# MainMaster.net
KiCad netlist of a schematic drawn in Altium Designer
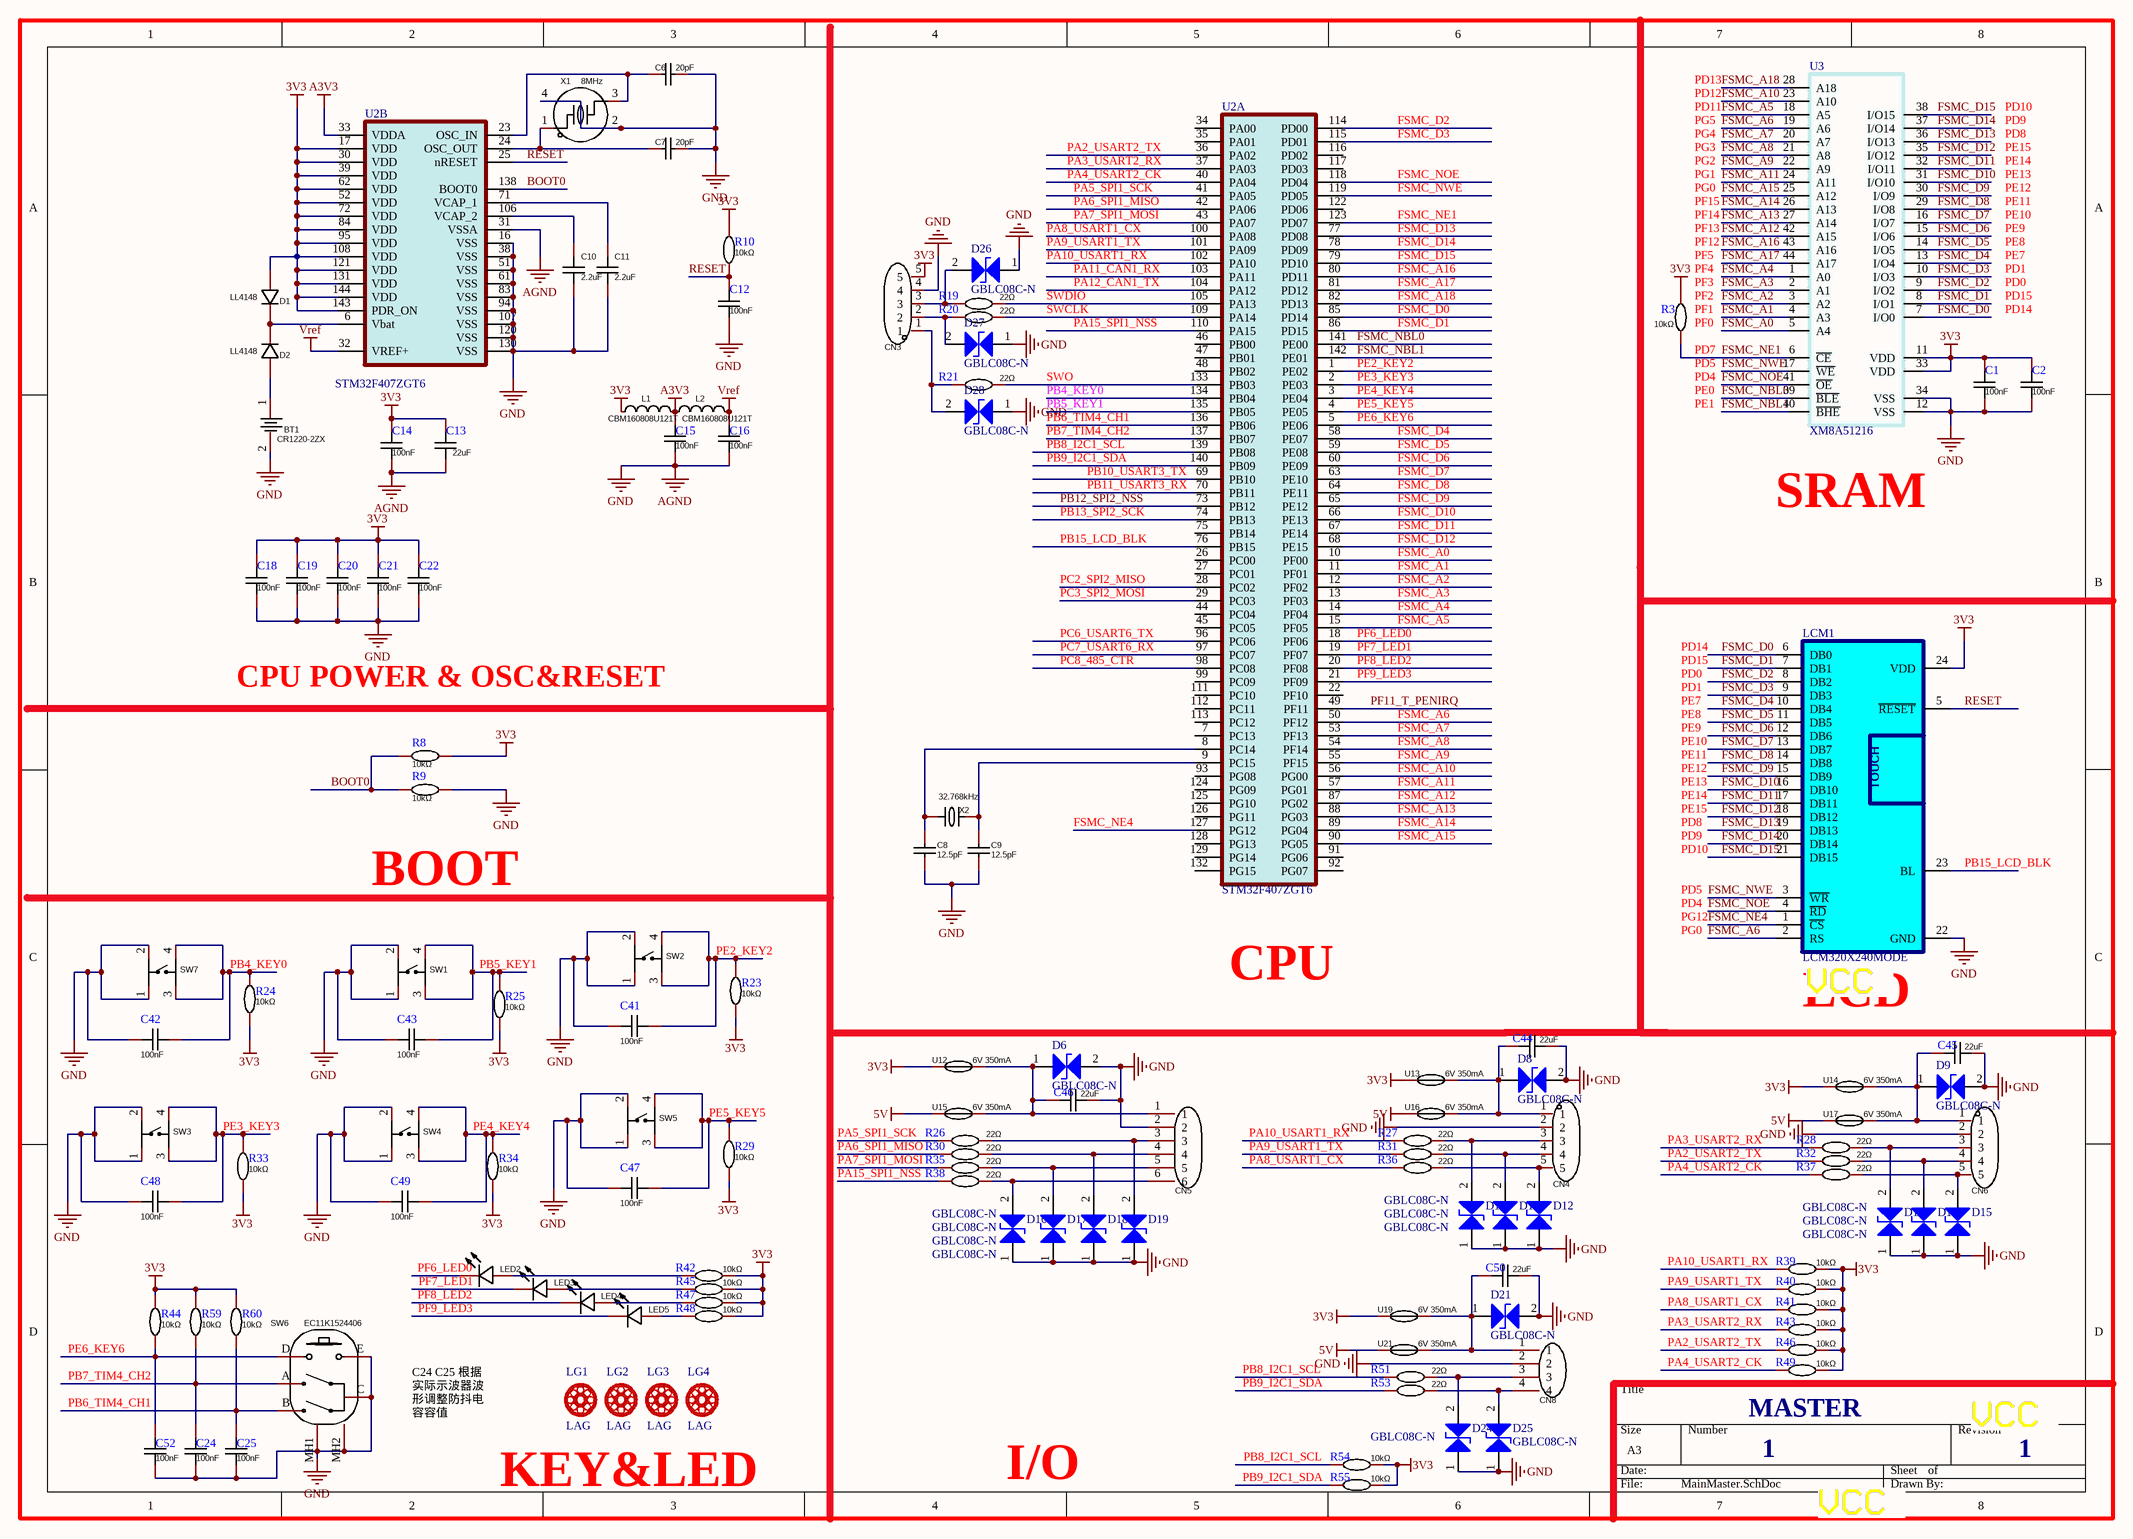
[diagram p0: MainMaster.SchDoc]

(export (version "E")
  (design (tool "Eeschema 10.0.6"))
  (components
    (comp (ref "BT1")
      (value "CR1220-2ZX")
      (footprint "LI1220_1")
      (fields (field (name "NAME") "CR1220-2ZX") (field (name "MANUFACTURER") "Q&J"))
      (libsource (lib "altium-import") (part "root_3_CR1220-2ZX_"))
    )
    (comp (ref "C1")
      (value "CC0603KRX7R9BB104")
      (footprint "C0603")
      (fields
        (field (name "NAME") "100nF")
        (field (name "MANUFACTURER") "YAGEO(国巨)")
        (field (name "TOLERANCE") "±10%")
      )
      (libsource (lib "altium-import") (part "root_1_CC0603KRX7R9BB104_"))
    )
    (comp (ref "C2")
      (value "CC0603KRX7R9BB104")
      (footprint "C0603")
      (fields
        (field (name "NAME") "100nF")
        (field (name "MANUFACTURER") "YAGEO(国巨)")
        (field (name "TOLERANCE") "±10%")
      )
      (libsource (lib "altium-import") (part "root_1_CC0603KRX7R9BB104_"))
    )
    (comp (ref "C6")
      (value "CC0603JRNPO9BN200")
      (footprint "C0603")
      (fields
        (field (name "NAME") "20pF")
        (field (name "MANUFACTURER") "YAGEO(国巨)")
        (field (name "TOLERANCE") "±5%")
      )
      (libsource (lib "altium-import") (part "root_0_CC0603JRNPO9BN200_"))
    )
    (comp (ref "C7")
      (value "CC0603JRNPO9BN200")
      (footprint "C0603")
      (fields
        (field (name "NAME") "20pF")
        (field (name "MANUFACTURER") "YAGEO(国巨)")
        (field (name "TOLERANCE") "±5%")
      )
      (libsource (lib "altium-import") (part "root_0_CC0603JRNPO9BN200_"))
    )
    (comp (ref "C8")
      (value "CC0603JRNPO9BN200")
      (footprint "C0603")
      (fields
        (field (name "NAME") "12.5pF")
        (field (name "MANUFACTURER") "YAGEO(国巨)")
        (field (name "TOLERANCE") "±5%")
      )
      (libsource (lib "altium-import") (part "root_1_CC0603JRNPO9BN200_"))
    )
    (comp (ref "C9")
      (value "CC0603JRNPO9BN200")
      (footprint "C0603")
      (fields
        (field (name "NAME") "12.5pF")
        (field (name "MANUFACTURER") "YAGEO(国巨)")
        (field (name "TOLERANCE") "±5%")
      )
      (libsource (lib "altium-import") (part "root_1_CC0603JRNPO9BN200_"))
    )
    (comp (ref "C10")
      (value "CL10A225KA8NNNC")
      (footprint "C0603")
      (fields
        (field (name "NAME") "2.2uF")
        (field (name "MANUFACTURER") "SAMSUNG(三星)")
        (field (name "TOLERANCE") "±10%")
      )
      (libsource (lib "altium-import") (part "root_1_CL10A225KA8NNNC_"))
    )
    (comp (ref "C11")
      (value "CL10A225KA8NNNC")
      (footprint "C0603")
      (fields
        (field (name "NAME") "2.2uF")
        (field (name "MANUFACTURER") "SAMSUNG(三星)")
        (field (name "TOLERANCE") "±10%")
      )
      (libsource (lib "altium-import") (part "root_1_CL10A225KA8NNNC_"))
    )
    (comp (ref "C12")
      (value "CC0603KRX7R9BB104")
      (footprint "C0603")
      (fields
        (field (name "NAME") "100nF")
        (field (name "MANUFACTURER") "YAGEO(国巨)")
        (field (name "TOLERANCE") "±10%")
      )
      (libsource (lib "altium-import") (part "root_1_CC0603KRX7R9BB104_"))
    )
    (comp (ref "C13")
      (value "CC0603KRX7R9BB104")
      (footprint "C1210")
      (fields
        (field (name "NAME") "22uF")
        (field (name "MANUFACTURER") "YAGEO(国巨)")
        (field (name "TOLERANCE") "±10%")
      )
      (libsource (lib "altium-import") (part "root_1_CC0603KRX7R9BB104_"))
    )
    (comp (ref "C14")
      (value "CC0603KRX7R9BB104")
      (footprint "C0603")
      (fields
        (field (name "NAME") "100nF")
        (field (name "MANUFACTURER") "YAGEO(国巨)")
        (field (name "TOLERANCE") "±10%")
      )
      (libsource (lib "altium-import") (part "root_1_CC0603KRX7R9BB104_"))
    )
    (comp (ref "C15")
      (value "CC0603KRX7R9BB104")
      (footprint "C0603")
      (fields
        (field (name "NAME") "100nF")
        (field (name "MANUFACTURER") "YAGEO(国巨)")
        (field (name "TOLERANCE") "±10%")
      )
      (libsource (lib "altium-import") (part "root_1_CC0603KRX7R9BB104_"))
    )
    (comp (ref "C16")
      (value "CC0603KRX7R9BB104")
      (footprint "C0603")
      (fields
        (field (name "NAME") "100nF")
        (field (name "MANUFACTURER") "YAGEO(国巨)")
        (field (name "TOLERANCE") "±10%")
      )
      (libsource (lib "altium-import") (part "root_1_CC0603KRX7R9BB104_"))
    )
    (comp (ref "C18")
      (value "CC0603KRX7R9BB104")
      (footprint "C0603")
      (fields
        (field (name "NAME") "100nF")
        (field (name "MANUFACTURER") "YAGEO(国巨)")
        (field (name "TOLERANCE") "±10%")
      )
      (libsource (lib "altium-import") (part "root_1_CC0603KRX7R9BB104_"))
    )
    (comp (ref "C19")
      (value "CC0603KRX7R9BB104")
      (footprint "C0603")
      (fields
        (field (name "NAME") "100nF")
        (field (name "MANUFACTURER") "YAGEO(国巨)")
        (field (name "TOLERANCE") "±10%")
      )
      (libsource (lib "altium-import") (part "root_1_CC0603KRX7R9BB104_"))
    )
    (comp (ref "C20")
      (value "CC0603KRX7R9BB104")
      (footprint "C0603")
      (fields
        (field (name "NAME") "100nF")
        (field (name "MANUFACTURER") "YAGEO(国巨)")
        (field (name "TOLERANCE") "±10%")
      )
      (libsource (lib "altium-import") (part "root_1_CC0603KRX7R9BB104_"))
    )
    (comp (ref "C21")
      (value "CC0603KRX7R9BB104")
      (footprint "C0603")
      (fields
        (field (name "NAME") "100nF")
        (field (name "MANUFACTURER") "YAGEO(国巨)")
        (field (name "TOLERANCE") "±10%")
      )
      (libsource (lib "altium-import") (part "root_1_CC0603KRX7R9BB104_"))
    )
    (comp (ref "C22")
      (value "CC0603KRX7R9BB104")
      (footprint "C0603")
      (fields
        (field (name "NAME") "100nF")
        (field (name "MANUFACTURER") "YAGEO(国巨)")
        (field (name "TOLERANCE") "±10%")
      )
      (libsource (lib "altium-import") (part "root_1_CC0603KRX7R9BB104_"))
    )
    (comp (ref "C24")
      (value "CC0603KRX7R9BB104")
      (footprint "C0603")
      (fields
        (field (name "NAME") "100nF")
        (field (name "MANUFACTURER") "YAGEO(国巨)")
        (field (name "TOLERANCE") "±10%")
      )
      (libsource (lib "altium-import") (part "root_3_CC0603KRX7R9BB104_"))
    )
    (comp (ref "C25")
      (value "CC0603KRX7R9BB104")
      (footprint "C0603")
      (fields
        (field (name "NAME") "100nF")
        (field (name "MANUFACTURER") "YAGEO(国巨)")
        (field (name "TOLERANCE") "±10%")
      )
      (libsource (lib "altium-import") (part "root_3_CC0603KRX7R9BB104_"))
    )
    (comp (ref "C41")
      (value "CC0603KRX7R9BB104")
      (footprint "C0603")
      (fields
        (field (name "NAME") "100nF")
        (field (name "MANUFACTURER") "YAGEO(国巨)")
        (field (name "TOLERANCE") "±10%")
      )
      (libsource (lib "altium-import") (part "root_2_CC0603KRX7R9BB104_"))
    )
    (comp (ref "C42")
      (value "CC0603KRX7R9BB104")
      (footprint "C0603")
      (fields
        (field (name "NAME") "100nF")
        (field (name "MANUFACTURER") "YAGEO(国巨)")
        (field (name "TOLERANCE") "±10%")
      )
      (libsource (lib "altium-import") (part "root_2_CC0603KRX7R9BB104_"))
    )
    (comp (ref "C43")
      (value "CC0603KRX7R9BB104")
      (footprint "C0603")
      (fields
        (field (name "NAME") "100nF")
        (field (name "MANUFACTURER") "YAGEO(国巨)")
        (field (name "TOLERANCE") "±10%")
      )
      (libsource (lib "altium-import") (part "root_2_CC0603KRX7R9BB104_"))
    )
    (comp (ref "C44")
      (value "CC0603KRX7R9BB104")
      (footprint "C1210")
      (fields
        (field (name "NAME") "22uF")
        (field (name "MANUFACTURER") "YAGEO(国巨)")
        (field (name "TOLERANCE") "±10%")
      )
      (libsource (lib "altium-import") (part "root_2_CC0603KRX7R9BB104_"))
    )
    (comp (ref "C45")
      (value "CC0603KRX7R9BB104")
      (footprint "C1210")
      (fields
        (field (name "NAME") "22uF")
        (field (name "MANUFACTURER") "YAGEO(国巨)")
        (field (name "TOLERANCE") "±10%")
      )
      (libsource (lib "altium-import") (part "root_2_CC0603KRX7R9BB104_"))
    )
    (comp (ref "C46")
      (value "CC0603KRX7R9BB104")
      (footprint "C1210")
      (fields
        (field (name "NAME") "22uF")
        (field (name "MANUFACTURER") "YAGEO(国巨)")
        (field (name "TOLERANCE") "±10%")
      )
      (libsource (lib "altium-import") (part "root_2_CC0603KRX7R9BB104_"))
    )
    (comp (ref "C47")
      (value "CC0603KRX7R9BB104")
      (footprint "C0603")
      (fields
        (field (name "NAME") "100nF")
        (field (name "MANUFACTURER") "YAGEO(国巨)")
        (field (name "TOLERANCE") "±10%")
      )
      (libsource (lib "altium-import") (part "root_2_CC0603KRX7R9BB104_"))
    )
    (comp (ref "C48")
      (value "CC0603KRX7R9BB104")
      (footprint "C0603")
      (fields
        (field (name "NAME") "100nF")
        (field (name "MANUFACTURER") "YAGEO(国巨)")
        (field (name "TOLERANCE") "±10%")
      )
      (libsource (lib "altium-import") (part "root_2_CC0603KRX7R9BB104_"))
    )
    (comp (ref "C49")
      (value "CC0603KRX7R9BB104")
      (footprint "C0603")
      (fields
        (field (name "NAME") "100nF")
        (field (name "MANUFACTURER") "YAGEO(国巨)")
        (field (name "TOLERANCE") "±10%")
      )
      (libsource (lib "altium-import") (part "root_2_CC0603KRX7R9BB104_"))
    )
    (comp (ref "C50")
      (value "CC0603KRX7R9BB104")
      (footprint "C1210")
      (fields
        (field (name "NAME") "22uF")
        (field (name "MANUFACTURER") "YAGEO(国巨)")
        (field (name "TOLERANCE") "±10%")
      )
      (libsource (lib "altium-import") (part "root_2_CC0603KRX7R9BB104_"))
    )
    (comp (ref "C52")
      (value "CC0603KRX7R9BB104")
      (footprint "C0603")
      (fields
        (field (name "NAME") "100nF")
        (field (name "MANUFACTURER") "YAGEO(国巨)")
        (field (name "TOLERANCE") "±10%")
      )
      (libsource (lib "altium-import") (part "root_3_CC0603KRX7R9BB104_"))
    )
    (comp (ref "CN3")
      (value "XH-5A")
      (footprint "XH2.5-5P")
      (fields (field (name "MANUFACTURER") "BOOMELE(博穆精密)"))
      (libsource (lib "altium-import") (part "root_2_XH-5A_"))
    )
    (comp (ref "CN4")
      (value "XH-5A")
      (footprint "XH2.5-5P")
      (fields (field (name "MANUFACTURER") "BOOMELE(博穆精密)"))
      (libsource (lib "altium-import") (part "root_0_XH-5A_"))
    )
    (comp (ref "CN5")
      (value "XH-6A")
      (footprint "XH2.5-6P")
      (fields (field (name "MANUFACTURER") "BOOMELE(博穆精密)"))
      (libsource (lib "altium-import") (part "root_0_mirrored_XH-6A_"))
    )
    (comp (ref "CN6")
      (value "XH-5A")
      (footprint "XH2.5-5P")
      (fields (field (name "MANUFACTURER") "BOOMELE(博穆精密)"))
      (libsource (lib "altium-import") (part "root_0_XH-5A_"))
    )
    (comp (ref "CN8")
      (value "XH-4A")
      (footprint "XH2.5-4P")
      (fields (field (name "MANUFACTURER") "BOOMELE(博穆精密)"))
      (libsource (lib "altium-import") (part "root_0_mirrored_XH-4A_"))
    )
    (comp (ref "D1")
      (value "LL4148_C84135")
      (footprint "MINI_MELF (LL34)")
      (fields
        (field (name "NAME") "LL4148")
        (field (name "MANUFACTURER") "onsemi(安森美)")
        (field (name "MANUFACTURER PART") "LL4148")
      )
      (libsource (lib "altium-import") (part "root_1_LL4148_C84135_"))
    )
    (comp (ref "D2")
      (value "LL4148_C84135")
      (footprint "MINI_MELF (LL34)")
      (fields
        (field (name "NAME") "LL4148")
        (field (name "MANUFACTURER") "onsemi(安森美)")
        (field (name "MANUFACTURER PART") "LL4148")
      )
      (libsource (lib "altium-import") (part "root_3_LL4148_C84135_"))
    )
    (comp (ref "D6")
      (value "GBLC08C-N")
      (footprint "SOD-323_L1.8-W1.3-LS2.5-BI")
      (description "LXES1UTAA1-157,0402,MURATA")
      (fields (field (name "NAME") "GBLC08C-N") (field (name "MANUFACTURER") "BORN伯恩半导体"))
      (libsource (lib "ErpMaterialData-U9") (part "DIODE ZENER2"))
    )
    (comp (ref "D8")
      (value "GBLC08C-N")
      (footprint "SOD-323_L1.8-W1.3-LS2.5-BI")
      (description "LXES1UTAA1-157,0402,MURATA")
      (fields (field (name "NAME") "GBLC08C-N") (field (name "MANUFACTURER") "BORN伯恩半导体"))
      (libsource (lib "ErpMaterialData-U9") (part "DIODE ZENER2"))
    )
    (comp (ref "D9")
      (value "GBLC08C-N")
      (footprint "SOD-323_L1.8-W1.3-LS2.5-BI")
      (description "LXES1UTAA1-157,0402,MURATA")
      (fields (field (name "NAME") "GBLC08C-N") (field (name "MANUFACTURER") "BORN伯恩半导体"))
      (libsource (lib "ErpMaterialData-U9") (part "DIODE ZENER2"))
    )
    (comp (ref "D10")
      (value "GBLC08C-N")
      (footprint "SOD-323_L1.8-W1.3-LS2.5-BI")
      (description "LXES1UTAA1-157,0402,MURATA")
      (fields (field (name "NAME") "GBLC08C-N") (field (name "MANUFACTURER") "BORN伯恩半导体"))
      (libsource (lib "ErpMaterialData-U9") (part "DIODE ZENER2"))
    )
    (comp (ref "D11")
      (value "GBLC08C-N")
      (footprint "SOD-323_L1.8-W1.3-LS2.5-BI")
      (description "LXES1UTAA1-157,0402,MURATA")
      (fields (field (name "NAME") "GBLC08C-N") (field (name "MANUFACTURER") "BORN伯恩半导体"))
      (libsource (lib "ErpMaterialData-U9") (part "DIODE ZENER2"))
    )
    (comp (ref "D12")
      (value "GBLC08C-N")
      (footprint "SOD-323_L1.8-W1.3-LS2.5-BI")
      (description "LXES1UTAA1-157,0402,MURATA")
      (fields (field (name "NAME") "GBLC08C-N") (field (name "MANUFACTURER") "BORN伯恩半导体"))
      (libsource (lib "ErpMaterialData-U9") (part "DIODE ZENER2"))
    )
    (comp (ref "D13")
      (value "GBLC08C-N")
      (footprint "SOD-323_L1.8-W1.3-LS2.5-BI")
      (description "LXES1UTAA1-157,0402,MURATA")
      (fields (field (name "NAME") "GBLC08C-N") (field (name "MANUFACTURER") "BORN伯恩半导体"))
      (libsource (lib "ErpMaterialData-U9") (part "DIODE ZENER2"))
    )
    (comp (ref "D14")
      (value "GBLC08C-N")
      (footprint "SOD-323_L1.8-W1.3-LS2.5-BI")
      (description "LXES1UTAA1-157,0402,MURATA")
      (fields (field (name "NAME") "GBLC08C-N") (field (name "MANUFACTURER") "BORN伯恩半导体"))
      (libsource (lib "ErpMaterialData-U9") (part "DIODE ZENER2"))
    )
    (comp (ref "D15")
      (value "GBLC08C-N")
      (footprint "SOD-323_L1.8-W1.3-LS2.5-BI")
      (description "LXES1UTAA1-157,0402,MURATA")
      (fields (field (name "NAME") "GBLC08C-N") (field (name "MANUFACTURER") "BORN伯恩半导体"))
      (libsource (lib "ErpMaterialData-U9") (part "DIODE ZENER2"))
    )
    (comp (ref "D16")
      (value "GBLC08C-N")
      (footprint "SOD-323_L1.8-W1.3-LS2.5-BI")
      (description "LXES1UTAA1-157,0402,MURATA")
      (fields (field (name "NAME") "GBLC08C-N") (field (name "MANUFACTURER") "BORN伯恩半导体"))
      (libsource (lib "ErpMaterialData-U9") (part "DIODE ZENER2"))
    )
    (comp (ref "D17")
      (value "GBLC08C-N")
      (footprint "SOD-323_L1.8-W1.3-LS2.5-BI")
      (description "LXES1UTAA1-157,0402,MURATA")
      (fields (field (name "NAME") "GBLC08C-N") (field (name "MANUFACTURER") "BORN伯恩半导体"))
      (libsource (lib "ErpMaterialData-U9") (part "DIODE ZENER2"))
    )
    (comp (ref "D18")
      (value "GBLC08C-N")
      (footprint "SOD-323_L1.8-W1.3-LS2.5-BI")
      (description "LXES1UTAA1-157,0402,MURATA")
      (fields (field (name "NAME") "GBLC08C-N") (field (name "MANUFACTURER") "BORN伯恩半导体"))
      (libsource (lib "ErpMaterialData-U9") (part "DIODE ZENER2"))
    )
    (comp (ref "D19")
      (value "GBLC08C-N")
      (footprint "SOD-323_L1.8-W1.3-LS2.5-BI")
      (description "LXES1UTAA1-157,0402,MURATA")
      (fields (field (name "NAME") "GBLC08C-N") (field (name "MANUFACTURER") "BORN伯恩半导体"))
      (libsource (lib "ErpMaterialData-U9") (part "DIODE ZENER2"))
    )
    (comp (ref "D21")
      (value "GBLC08C-N")
      (footprint "SOD-323_L1.8-W1.3-LS2.5-BI")
      (description "LXES1UTAA1-157,0402,MURATA")
      (fields (field (name "NAME") "GBLC08C-N") (field (name "MANUFACTURER") "BORN伯恩半导体"))
      (libsource (lib "ErpMaterialData-U9") (part "DIODE ZENER2"))
    )
    (comp (ref "D24")
      (value "GBLC08C-N")
      (footprint "SOD-323_L1.8-W1.3-LS2.5-BI")
      (description "LXES1UTAA1-157,0402,MURATA")
      (fields (field (name "NAME") "GBLC08C-N") (field (name "MANUFACTURER") "BORN伯恩半导体"))
      (libsource (lib "ErpMaterialData-U9") (part "DIODE ZENER2"))
    )
    (comp (ref "D25")
      (value "GBLC08C-N")
      (footprint "SOD-323_L1.8-W1.3-LS2.5-BI")
      (description "LXES1UTAA1-157,0402,MURATA")
      (fields (field (name "NAME") "GBLC08C-N") (field (name "MANUFACTURER") "BORN伯恩半导体"))
      (libsource (lib "ErpMaterialData-U9") (part "DIODE ZENER2"))
    )
    (comp (ref "D26")
      (value "GBLC08C-N")
      (footprint "SOD-323_L1.8-W1.3-LS2.5-BI")
      (description "LXES1UTAA1-157,0402,MURATA")
      (fields (field (name "NAME") "GBLC08C-N") (field (name "MANUFACTURER") "BORN伯恩半导体"))
      (libsource (lib "ErpMaterialData-U9") (part "DIODE ZENER2"))
    )
    (comp (ref "D27")
      (value "GBLC08C-N")
      (footprint "SOD-323_L1.8-W1.3-LS2.5-BI")
      (description "LXES1UTAA1-157,0402,MURATA")
      (fields (field (name "NAME") "GBLC08C-N") (field (name "MANUFACTURER") "BORN伯恩半导体"))
      (libsource (lib "ErpMaterialData-U9") (part "DIODE ZENER2"))
    )
    (comp (ref "D28")
      (value "GBLC08C-N")
      (footprint "SOD-323_L1.8-W1.3-LS2.5-BI")
      (description "LXES1UTAA1-157,0402,MURATA")
      (fields (field (name "NAME") "GBLC08C-N") (field (name "MANUFACTURER") "BORN伯恩半导体"))
      (libsource (lib "ErpMaterialData-U9") (part "DIODE ZENER2"))
    )
    (comp (ref "L1")
      (value "CBM160808U121T")
      (footprint "L0603")
      (fields
        (field (name "NAME") "CBM160808U121T")
        (field (name "MANUFACTURER") "FH(风华)")
        (field (name "TOLERANCE") "±25%")
      )
      (libsource (lib "altium-import") (part "root_0_CBM160808U121T_"))
    )
    (comp (ref "L2")
      (value "CBM160808U121T")
      (footprint "L0603")
      (fields
        (field (name "NAME") "CBM160808U121T")
        (field (name "MANUFACTURER") "FH(风华)")
        (field (name "TOLERANCE") "±25%")
      )
      (libsource (lib "altium-import") (part "root_0_CBM160808U121T_"))
    )
    (comp (ref "LCM1")
      (value "LCM320X240MODE")
      (footprint "LCM2.8 MODE")
      (libsource (lib "华南师范控制板") (part "LCM320X240MODE"))
    )
    (comp (ref "LED2")
      (value "17-21SYGC/S530-E3/TR8")
      (footprint "LED 0805G")
      (fields (field (name "MANUFACTURER") "EVERLIGHT(亿光)"))
      (libsource (lib "altium-import") (part "root_0_17-21SYGC/S530-E3/TR8_"))
    )
    (comp (ref "LED3")
      (value "17-21SYGC/S530-E3/TR8")
      (footprint "LED 0805G")
      (fields (field (name "MANUFACTURER") "EVERLIGHT(亿光)"))
      (libsource (lib "altium-import") (part "root_0_17-21SYGC/S530-E3/TR8_"))
    )
    (comp (ref "LED4")
      (value "17-21SYGC/S530-E3/TR8")
      (footprint "LED 0805G")
      (fields (field (name "MANUFACTURER") "EVERLIGHT(亿光)"))
      (libsource (lib "altium-import") (part "root_0_17-21SYGC/S530-E3/TR8_"))
    )
    (comp (ref "LED5")
      (value "17-21SYGC/S530-E3/TR8")
      (footprint "LED 0805G")
      (fields (field (name "MANUFACTURER") "EVERLIGHT(亿光)"))
      (libsource (lib "altium-import") (part "root_0_17-21SYGC/S530-E3/TR8_"))
    )
    (comp (ref "LG1") (value "LAG") (footprint "LAGVAL") (libsource (lib "3DGeneral") (part "LAGVAL")))
    (comp (ref "LG2") (value "LAG") (footprint "LAGVAL") (libsource (lib "3DGeneral") (part "LAGVAL")))
    (comp (ref "LG3") (value "LAG") (footprint "LAGVAL") (libsource (lib "3DGeneral") (part "LAGVAL")))
    (comp (ref "LG4") (value "LAG") (footprint "LAGVAL") (libsource (lib "3DGeneral") (part "LAGVAL")))
    (comp (ref "R3")
      (value "10kΩ")
      (footprint "R0603")
      (fields
        (field (name "MANUFACTURER") "UNI-ROYAL(厚声)")
        (field (name "MANUFACTURER PART") "0603WAF5113T5E")
        (field (name "TOLERANCE") "±1%")
      )
      (libsource (lib "altium-import") (part "root_1_0603WAF5113T5E_"))
    )
    (comp (ref "R8")
      (value "10kΩ")
      (footprint "R0603")
      (fields
        (field (name "MANUFACTURER") "UNI-ROYAL(厚声)")
        (field (name "MANUFACTURER PART") "0603WAF5113T5E")
        (field (name "TOLERANCE") "±1%")
      )
      (libsource (lib "altium-import") (part "root_0_0603WAF5113T5E_"))
    )
    (comp (ref "R9")
      (value "10kΩ")
      (footprint "R0603")
      (fields
        (field (name "MANUFACTURER") "UNI-ROYAL(厚声)")
        (field (name "MANUFACTURER PART") "0603WAF5113T5E")
        (field (name "TOLERANCE") "±1%")
      )
      (libsource (lib "altium-import") (part "root_0_0603WAF5113T5E_"))
    )
    (comp (ref "R10")
      (value "10kΩ")
      (footprint "R0603")
      (fields
        (field (name "MANUFACTURER") "UNI-ROYAL(厚声)")
        (field (name "MANUFACTURER PART") "0603WAF5113T5E")
        (field (name "TOLERANCE") "±1%")
      )
      (libsource (lib "altium-import") (part "root_3_0603WAF5113T5E_"))
    )
    (comp (ref "R19")
      (value "22Ω")
      (footprint "R0603")
      (fields
        (field (name "MANUFACTURER") "UNI-ROYAL(厚声)")
        (field (name "MANUFACTURER PART") "0603WAF5113T5E")
        (field (name "TOLERANCE") "±1%")
      )
      (libsource (lib "altium-import") (part "root_2_0603WAF5113T5E_"))
    )
    (comp (ref "R20")
      (value "22Ω")
      (footprint "R0603")
      (fields
        (field (name "MANUFACTURER") "UNI-ROYAL(厚声)")
        (field (name "MANUFACTURER PART") "0603WAF5113T5E")
        (field (name "TOLERANCE") "±1%")
      )
      (libsource (lib "altium-import") (part "root_2_0603WAF5113T5E_"))
    )
    (comp (ref "R21")
      (value "22Ω")
      (footprint "R0603")
      (fields
        (field (name "MANUFACTURER") "UNI-ROYAL(厚声)")
        (field (name "MANUFACTURER PART") "0603WAF5113T5E")
        (field (name "TOLERANCE") "±1%")
      )
      (libsource (lib "altium-import") (part "root_2_0603WAF5113T5E_"))
    )
    (comp (ref "R23")
      (value "10kΩ")
      (footprint "R0603")
      (fields
        (field (name "MANUFACTURER") "UNI-ROYAL(厚声)")
        (field (name "MANUFACTURER PART") "0603WAF5113T5E")
        (field (name "TOLERANCE") "±1%")
      )
      (libsource (lib "altium-import") (part "root_1_0603WAF5113T5E_"))
    )
    (comp (ref "R24")
      (value "10kΩ")
      (footprint "R0603")
      (fields
        (field (name "MANUFACTURER") "UNI-ROYAL(厚声)")
        (field (name "MANUFACTURER PART") "0603WAF5113T5E")
        (field (name "TOLERANCE") "±1%")
      )
      (libsource (lib "altium-import") (part "root_1_0603WAF5113T5E_"))
    )
    (comp (ref "R25")
      (value "10kΩ")
      (footprint "R0603")
      (fields
        (field (name "MANUFACTURER") "UNI-ROYAL(厚声)")
        (field (name "MANUFACTURER PART") "0603WAF5113T5E")
        (field (name "TOLERANCE") "±1%")
      )
      (libsource (lib "altium-import") (part "root_1_0603WAF5113T5E_"))
    )
    (comp (ref "R26")
      (value "22Ω")
      (footprint "R0603")
      (fields
        (field (name "MANUFACTURER") "UNI-ROYAL(厚声)")
        (field (name "MANUFACTURER PART") "0603WAF5113T5E")
        (field (name "TOLERANCE") "±1%")
      )
      (libsource (lib "altium-import") (part "root_2_0603WAF5113T5E_"))
    )
    (comp (ref "R27")
      (value "22Ω")
      (footprint "R0603")
      (fields
        (field (name "MANUFACTURER") "UNI-ROYAL(厚声)")
        (field (name "MANUFACTURER PART") "0603WAF5113T5E")
        (field (name "TOLERANCE") "±1%")
      )
      (libsource (lib "altium-import") (part "root_2_0603WAF5113T5E_"))
    )
    (comp (ref "R28")
      (value "22Ω")
      (footprint "R0603")
      (fields
        (field (name "MANUFACTURER") "UNI-ROYAL(厚声)")
        (field (name "MANUFACTURER PART") "0603WAF5113T5E")
        (field (name "TOLERANCE") "±1%")
      )
      (libsource (lib "altium-import") (part "root_2_0603WAF5113T5E_"))
    )
    (comp (ref "R29")
      (value "10kΩ")
      (footprint "R0603")
      (fields
        (field (name "MANUFACTURER") "UNI-ROYAL(厚声)")
        (field (name "MANUFACTURER PART") "0603WAF5113T5E")
        (field (name "TOLERANCE") "±1%")
      )
      (libsource (lib "altium-import") (part "root_1_0603WAF5113T5E_"))
    )
    (comp (ref "R30")
      (value "22Ω")
      (footprint "R0603")
      (fields
        (field (name "MANUFACTURER") "UNI-ROYAL(厚声)")
        (field (name "MANUFACTURER PART") "0603WAF5113T5E")
        (field (name "TOLERANCE") "±1%")
      )
      (libsource (lib "altium-import") (part "root_2_0603WAF5113T5E_"))
    )
    (comp (ref "R31")
      (value "22Ω")
      (footprint "R0603")
      (fields
        (field (name "MANUFACTURER") "UNI-ROYAL(厚声)")
        (field (name "MANUFACTURER PART") "0603WAF5113T5E")
        (field (name "TOLERANCE") "±1%")
      )
      (libsource (lib "altium-import") (part "root_2_0603WAF5113T5E_"))
    )
    (comp (ref "R32")
      (value "22Ω")
      (footprint "R0603")
      (fields
        (field (name "MANUFACTURER") "UNI-ROYAL(厚声)")
        (field (name "MANUFACTURER PART") "0603WAF5113T5E")
        (field (name "TOLERANCE") "±1%")
      )
      (libsource (lib "altium-import") (part "root_2_0603WAF5113T5E_"))
    )
    (comp (ref "R33")
      (value "10kΩ")
      (footprint "R0603")
      (fields
        (field (name "MANUFACTURER") "UNI-ROYAL(厚声)")
        (field (name "MANUFACTURER PART") "0603WAF5113T5E")
        (field (name "TOLERANCE") "±1%")
      )
      (libsource (lib "altium-import") (part "root_1_0603WAF5113T5E_"))
    )
    (comp (ref "R34")
      (value "10kΩ")
      (footprint "R0603")
      (fields
        (field (name "MANUFACTURER") "UNI-ROYAL(厚声)")
        (field (name "MANUFACTURER PART") "0603WAF5113T5E")
        (field (name "TOLERANCE") "±1%")
      )
      (libsource (lib "altium-import") (part "root_1_0603WAF5113T5E_"))
    )
    (comp (ref "R35")
      (value "22Ω")
      (footprint "R0603")
      (fields
        (field (name "MANUFACTURER") "UNI-ROYAL(厚声)")
        (field (name "MANUFACTURER PART") "0603WAF5113T5E")
        (field (name "TOLERANCE") "±1%")
      )
      (libsource (lib "altium-import") (part "root_2_0603WAF5113T5E_"))
    )
    (comp (ref "R36")
      (value "22Ω")
      (footprint "R0603")
      (fields
        (field (name "MANUFACTURER") "UNI-ROYAL(厚声)")
        (field (name "MANUFACTURER PART") "0603WAF5113T5E")
        (field (name "TOLERANCE") "±1%")
      )
      (libsource (lib "altium-import") (part "root_2_0603WAF5113T5E_"))
    )
    (comp (ref "R37")
      (value "22Ω")
      (footprint "R0603")
      (fields
        (field (name "MANUFACTURER") "UNI-ROYAL(厚声)")
        (field (name "MANUFACTURER PART") "0603WAF5113T5E")
        (field (name "TOLERANCE") "±1%")
      )
      (libsource (lib "altium-import") (part "root_2_0603WAF5113T5E_"))
    )
    (comp (ref "R38")
      (value "22Ω")
      (footprint "R0603")
      (fields
        (field (name "MANUFACTURER") "UNI-ROYAL(厚声)")
        (field (name "MANUFACTURER PART") "0603WAF5113T5E")
        (field (name "TOLERANCE") "±1%")
      )
      (libsource (lib "altium-import") (part "root_2_0603WAF5113T5E_"))
    )
    (comp (ref "R39")
      (value "10kΩ")
      (footprint "R0603")
      (fields
        (field (name "MANUFACTURER") "UNI-ROYAL(厚声)")
        (field (name "MANUFACTURER PART") "0603WAF5113T5E")
        (field (name "TOLERANCE") "±1%")
      )
      (libsource (lib "altium-import") (part "root_2_0603WAF5113T5E_"))
    )
    (comp (ref "R40")
      (value "10kΩ")
      (footprint "R0603")
      (fields
        (field (name "MANUFACTURER") "UNI-ROYAL(厚声)")
        (field (name "MANUFACTURER PART") "0603WAF5113T5E")
        (field (name "TOLERANCE") "±1%")
      )
      (libsource (lib "altium-import") (part "root_2_0603WAF5113T5E_"))
    )
    (comp (ref "R41")
      (value "10kΩ")
      (footprint "R0603")
      (fields
        (field (name "MANUFACTURER") "UNI-ROYAL(厚声)")
        (field (name "MANUFACTURER PART") "0603WAF5113T5E")
        (field (name "TOLERANCE") "±1%")
      )
      (libsource (lib "altium-import") (part "root_2_0603WAF5113T5E_"))
    )
    (comp (ref "R42")
      (value "10kΩ")
      (footprint "R0603")
      (fields
        (field (name "MANUFACTURER") "UNI-ROYAL(厚声)")
        (field (name "MANUFACTURER PART") "0603WAF5113T5E")
        (field (name "TOLERANCE") "±1%")
      )
      (libsource (lib "altium-import") (part "root_2_0603WAF5113T5E_"))
    )
    (comp (ref "R43")
      (value "10kΩ")
      (footprint "R0603")
      (fields
        (field (name "MANUFACTURER") "UNI-ROYAL(厚声)")
        (field (name "MANUFACTURER PART") "0603WAF5113T5E")
        (field (name "TOLERANCE") "±1%")
      )
      (libsource (lib "altium-import") (part "root_2_0603WAF5113T5E_"))
    )
    (comp (ref "R44")
      (value "10kΩ")
      (footprint "R0603")
      (fields
        (field (name "MANUFACTURER") "UNI-ROYAL(厚声)")
        (field (name "MANUFACTURER PART") "0603WAF5113T5E")
        (field (name "TOLERANCE") "±1%")
      )
      (libsource (lib "altium-import") (part "root_1_0603WAF5113T5E_"))
    )
    (comp (ref "R45")
      (value "10kΩ")
      (footprint "R0603")
      (fields
        (field (name "MANUFACTURER") "UNI-ROYAL(厚声)")
        (field (name "MANUFACTURER PART") "0603WAF5113T5E")
        (field (name "TOLERANCE") "±1%")
      )
      (libsource (lib "altium-import") (part "root_2_0603WAF5113T5E_"))
    )
    (comp (ref "R46")
      (value "10kΩ")
      (footprint "R0603")
      (fields
        (field (name "MANUFACTURER") "UNI-ROYAL(厚声)")
        (field (name "MANUFACTURER PART") "0603WAF5113T5E")
        (field (name "TOLERANCE") "±1%")
      )
      (libsource (lib "altium-import") (part "root_2_0603WAF5113T5E_"))
    )
    (comp (ref "R47")
      (value "10kΩ")
      (footprint "R0603")
      (fields
        (field (name "MANUFACTURER") "UNI-ROYAL(厚声)")
        (field (name "MANUFACTURER PART") "0603WAF5113T5E")
        (field (name "TOLERANCE") "±1%")
      )
      (libsource (lib "altium-import") (part "root_2_0603WAF5113T5E_"))
    )
    (comp (ref "R48")
      (value "10kΩ")
      (footprint "R0603")
      (fields
        (field (name "MANUFACTURER") "UNI-ROYAL(厚声)")
        (field (name "MANUFACTURER PART") "0603WAF5113T5E")
        (field (name "TOLERANCE") "±1%")
      )
      (libsource (lib "altium-import") (part "root_2_0603WAF5113T5E_"))
    )
    (comp (ref "R49")
      (value "10kΩ")
      (footprint "R0603")
      (fields
        (field (name "MANUFACTURER") "UNI-ROYAL(厚声)")
        (field (name "MANUFACTURER PART") "0603WAF5113T5E")
        (field (name "TOLERANCE") "±1%")
      )
      (libsource (lib "altium-import") (part "root_2_0603WAF5113T5E_"))
    )
    (comp (ref "R51")
      (value "22Ω")
      (footprint "R0603")
      (fields
        (field (name "MANUFACTURER") "UNI-ROYAL(厚声)")
        (field (name "MANUFACTURER PART") "0603WAF5113T5E")
        (field (name "TOLERANCE") "±1%")
      )
      (libsource (lib "altium-import") (part "root_2_0603WAF5113T5E_"))
    )
    (comp (ref "R53")
      (value "22Ω")
      (footprint "R0603")
      (fields
        (field (name "MANUFACTURER") "UNI-ROYAL(厚声)")
        (field (name "MANUFACTURER PART") "0603WAF5113T5E")
        (field (name "TOLERANCE") "±1%")
      )
      (libsource (lib "altium-import") (part "root_2_0603WAF5113T5E_"))
    )
    (comp (ref "R54")
      (value "10kΩ")
      (footprint "R0603")
      (fields
        (field (name "MANUFACTURER") "UNI-ROYAL(厚声)")
        (field (name "MANUFACTURER PART") "0603WAF5113T5E")
        (field (name "TOLERANCE") "±1%")
      )
      (libsource (lib "altium-import") (part "root_2_0603WAF5113T5E_"))
    )
    (comp (ref "R55")
      (value "10kΩ")
      (footprint "R0603")
      (fields
        (field (name "MANUFACTURER") "UNI-ROYAL(厚声)")
        (field (name "MANUFACTURER PART") "0603WAF5113T5E")
        (field (name "TOLERANCE") "±1%")
      )
      (libsource (lib "altium-import") (part "root_2_0603WAF5113T5E_"))
    )
    (comp (ref "R59")
      (value "10kΩ")
      (footprint "R0603")
      (fields
        (field (name "MANUFACTURER") "UNI-ROYAL(厚声)")
        (field (name "MANUFACTURER PART") "0603WAF5113T5E")
        (field (name "TOLERANCE") "±1%")
      )
      (libsource (lib "altium-import") (part "root_1_0603WAF5113T5E_"))
    )
    (comp (ref "R60")
      (value "10kΩ")
      (footprint "R0603")
      (fields
        (field (name "MANUFACTURER") "UNI-ROYAL(厚声)")
        (field (name "MANUFACTURER PART") "0603WAF5113T5E")
        (field (name "TOLERANCE") "±1%")
      )
      (libsource (lib "altium-import") (part "root_1_0603WAF5113T5E_"))
    )
    (comp (ref "SW1")
      (value "KH-6X6X5H-STM")
      (footprint "TSW DIP-12*12*7")
      (fields (field (name "MANUFACTURER") "kinghelm(金航标)"))
      (libsource (lib "altium-import") (part "root_1_KH-6X6X5H-STM_"))
    )
    (comp (ref "SW2")
      (value "KH-6X6X5H-STM")
      (footprint "TSW DIP-12*12*7")
      (fields (field (name "MANUFACTURER") "kinghelm(金航标)"))
      (libsource (lib "altium-import") (part "root_1_KH-6X6X5H-STM_"))
    )
    (comp (ref "SW3")
      (value "KH-6X6X5H-STM")
      (footprint "TSW DIP-12*12*7")
      (fields (field (name "MANUFACTURER") "kinghelm(金航标)"))
      (libsource (lib "altium-import") (part "root_1_KH-6X6X5H-STM_"))
    )
    (comp (ref "SW4")
      (value "KH-6X6X5H-STM")
      (footprint "TSW DIP-12*12*7")
      (fields (field (name "MANUFACTURER") "kinghelm(金航标)"))
      (libsource (lib "altium-import") (part "root_1_KH-6X6X5H-STM_"))
    )
    (comp (ref "SW5")
      (value "KH-6X6X5H-STM")
      (footprint "TSW DIP-12*12*7")
      (fields (field (name "MANUFACTURER") "kinghelm(金航标)"))
      (libsource (lib "altium-import") (part "root_1_KH-6X6X5H-STM_"))
    )
    (comp (ref "SW6")
      (value "EC11K1524406")
      (footprint "SW-TH_EC11K1524406")
      (fields (field (name "NAME") "EC11K1524406") (field (name "MANUFACTURER") "ALPSALPINE(阿尔卑斯阿尔派)"))
      (libsource (lib "altium-import") (part "root_0_EC11K1524406_"))
    )
    (comp (ref "SW7")
      (value "KH-6X6X5H-STM")
      (footprint "TSW DIP-12*12*7")
      (fields (field (name "MANUFACTURER") "kinghelm(金航标)"))
      (libsource (lib "altium-import") (part "root_1_KH-6X6X5H-STM_"))
    )
    (comp (ref "U2")
      (value "STM32F407ZGT6")
      (footprint "STM32F407ZET6_TQFP144")
      (description "STM32F407ZET6")
      (fields (field (name "NAME") "STM32F407ZGT6") (field (name "MANUFACTURER") "ST(意法半导体)"))
      (libsource (lib "3DGeneral") (part "STM32F407ZET6"))
    )
    (comp (ref "U3")
      (value "XM8A51216")
      (footprint "IS62WV51216BLL_TSOP44")
      (libsource (lib "PCB_Project") (part "IS64WV51216BLL-10MA3"))
    )
    (comp (ref "U12")
      (value "0603L035YR")
      (footprint "F0603")
      (fields (field (name "LCSC PART NAME") "6V 350mA") (field (name "MANUFACTURER") "Littelfuse(美国力特)"))
      (libsource (lib "altium-import") (part "root_0_0603L035YR_"))
    )
    (comp (ref "U13")
      (value "0603L035YR")
      (footprint "F0603")
      (fields (field (name "LCSC PART NAME") "6V 350mA") (field (name "MANUFACTURER") "Littelfuse(美国力特)"))
      (libsource (lib "altium-import") (part "root_0_0603L035YR_"))
    )
    (comp (ref "U14")
      (value "0603L035YR")
      (footprint "F0603")
      (fields (field (name "LCSC PART NAME") "6V 350mA") (field (name "MANUFACTURER") "Littelfuse(美国力特)"))
      (libsource (lib "altium-import") (part "root_0_0603L035YR_"))
    )
    (comp (ref "U15")
      (value "0603L035YR")
      (footprint "F0603")
      (fields (field (name "LCSC PART NAME") "6V 350mA") (field (name "MANUFACTURER") "Littelfuse(美国力特)"))
      (libsource (lib "altium-import") (part "root_0_0603L035YR_"))
    )
    (comp (ref "U16")
      (value "0603L035YR")
      (footprint "F0603")
      (fields (field (name "LCSC PART NAME") "6V 350mA") (field (name "MANUFACTURER") "Littelfuse(美国力特)"))
      (libsource (lib "altium-import") (part "root_0_0603L035YR_"))
    )
    (comp (ref "U17")
      (value "0603L035YR")
      (footprint "F0603")
      (fields (field (name "LCSC PART NAME") "6V 350mA") (field (name "MANUFACTURER") "Littelfuse(美国力特)"))
      (libsource (lib "altium-import") (part "root_0_0603L035YR_"))
    )
    (comp (ref "U19")
      (value "0603L035YR")
      (footprint "F0603")
      (fields (field (name "LCSC PART NAME") "6V 350mA") (field (name "MANUFACTURER") "Littelfuse(美国力特)"))
      (libsource (lib "altium-import") (part "root_0_0603L035YR_"))
    )
    (comp (ref "U21")
      (value "0603L035YR")
      (footprint "F0603")
      (fields (field (name "LCSC PART NAME") "6V 350mA") (field (name "MANUFACTURER") "Littelfuse(美国力特)"))
      (libsource (lib "altium-import") (part "root_0_0603L035YR_"))
    )
    (comp (ref "X1")
      (value "X32258MSB4SI")
      (footprint "OSC 3225-4P")
      (fields (field (name "NAME") "8MHz") (field (name "MANUFACTURER") "YXC(扬兴晶振)"))
      (libsource (lib "altium-import") (part "root_0_X32258MSB4SI_"))
    )
    (comp (ref "X2")
      (value "X321532768KGD2SI")
      (footprint "CR_3215_32768")
      (fields (field (name "NAME") "32.768kHz") (field (name "MANUFACTURER") "YXC(扬兴晶振)"))
      (libsource (lib "altium-import") (part "root_0_X321532768KGD2SI_"))
    )
  )
  (nets
    (net (code "1") (name "/BOOT0") (class "Default")
      (node (ref "R8") (pin "1") (pinfunction "1_1") (pintype "passive"))
      (node (ref "R9") (pin "1") (pinfunction "1_1") (pintype "passive"))
      (node (ref "U2") (pin "138") (pinfunction "BOOT0_138") (pintype "passive"))
    )
    (net (code "2") (name "/FSMC_A0") (class "Default")
      (node (ref "U2") (pin "10") (pinfunction "PF00_10") (pintype "passive"))
      (node (ref "U3") (pin "5") (pinfunction "A4_5") (pintype "passive"))
    )
    (net (code "3") (name "/FSMC_A1") (class "Default")
      (node (ref "U2") (pin "11") (pinfunction "PF01_11") (pintype "passive"))
      (node (ref "U3") (pin "4") (pinfunction "A3_4") (pintype "passive"))
    )
    (net (code "4") (name "/FSMC_A2") (class "Default")
      (node (ref "U2") (pin "12") (pinfunction "PF02_12") (pintype "passive"))
      (node (ref "U3") (pin "3") (pinfunction "A2_3") (pintype "passive"))
    )
    (net (code "5") (name "/FSMC_A3") (class "Default")
      (node (ref "U2") (pin "13") (pinfunction "PF03_13") (pintype "passive"))
      (node (ref "U3") (pin "2") (pinfunction "A1_2") (pintype "passive"))
    )
    (net (code "6") (name "/FSMC_A4") (class "Default")
      (node (ref "U2") (pin "14") (pinfunction "PF04_14") (pintype "passive"))
      (node (ref "U3") (pin "1") (pinfunction "A0_1") (pintype "passive"))
    )
    (net (code "7") (name "/FSMC_A5") (class "Default")
      (node (ref "U2") (pin "15") (pinfunction "PF05_15") (pintype "passive"))
      (node (ref "U3") (pin "18") (pinfunction "A5_18") (pintype "passive"))
    )
    (net (code "8") (name "/FSMC_A6") (class "Default")
      (node (ref "LCM1") (pin "2") (pinfunction "RS_2") (pintype "passive"))
      (node (ref "U2") (pin "50") (pinfunction "PF12_50") (pintype "passive"))
      (node (ref "U3") (pin "19") (pinfunction "A6_19") (pintype "passive"))
    )
    (net (code "9") (name "/FSMC_A7") (class "Default")
      (node (ref "U2") (pin "53") (pinfunction "PF13_53") (pintype "passive"))
      (node (ref "U3") (pin "20") (pinfunction "A7_20") (pintype "passive"))
    )
    (net (code "10") (name "/FSMC_A8") (class "Default")
      (node (ref "U2") (pin "54") (pinfunction "PF14_54") (pintype "passive"))
      (node (ref "U3") (pin "21") (pinfunction "A8_21") (pintype "passive"))
    )
    (net (code "11") (name "/FSMC_A9") (class "Default")
      (node (ref "U2") (pin "55") (pinfunction "PF15_55") (pintype "passive"))
      (node (ref "U3") (pin "22") (pinfunction "A9_22") (pintype "passive"))
    )
    (net (code "12") (name "/FSMC_A10") (class "Default")
      (node (ref "U2") (pin "56") (pinfunction "PG00_56") (pintype "passive"))
      (node (ref "U3") (pin "23") (pinfunction "A10_23") (pintype "passive"))
    )
    (net (code "13") (name "/FSMC_A11") (class "Default")
      (node (ref "U2") (pin "57") (pinfunction "PG01_57") (pintype "passive"))
      (node (ref "U3") (pin "24") (pinfunction "A11_24") (pintype "passive"))
    )
    (net (code "14") (name "/FSMC_A12") (class "Default")
      (node (ref "U2") (pin "87") (pinfunction "PG02_87") (pintype "passive"))
      (node (ref "U3") (pin "42") (pinfunction "A15_42") (pintype "passive"))
    )
    (net (code "15") (name "/FSMC_A13") (class "Default")
      (node (ref "U2") (pin "88") (pinfunction "PG03_88") (pintype "passive"))
      (node (ref "U3") (pin "27") (pinfunction "A14_27") (pintype "passive"))
    )
    (net (code "16") (name "/FSMC_A14") (class "Default")
      (node (ref "U2") (pin "89") (pinfunction "PG04_89") (pintype "passive"))
      (node (ref "U3") (pin "26") (pinfunction "A13_26") (pintype "passive"))
    )
    (net (code "17") (name "/FSMC_A15") (class "Default")
      (node (ref "U2") (pin "90") (pinfunction "PG05_90") (pintype "passive"))
      (node (ref "U3") (pin "25") (pinfunction "A12_25") (pintype "passive"))
    )
    (net (code "18") (name "/FSMC_A16") (class "Default")
      (node (ref "U2") (pin "80") (pinfunction "PD11_80") (pintype "passive"))
      (node (ref "U3") (pin "43") (pinfunction "A16_43") (pintype "passive"))
    )
    (net (code "19") (name "/FSMC_A17") (class "Default")
      (node (ref "U2") (pin "81") (pinfunction "PD12_81") (pintype "passive"))
      (node (ref "U3") (pin "44") (pinfunction "A17_44") (pintype "passive"))
    )
    (net (code "20") (name "/FSMC_A18") (class "Default")
      (node (ref "U2") (pin "82") (pinfunction "PD13_82") (pintype "passive"))
      (node (ref "U3") (pin "28") (pinfunction "A18_28") (pintype "passive"))
    )
    (net (code "21") (name "/FSMC_D0") (class "Default")
      (node (ref "LCM1") (pin "6") (pinfunction "DB0_6") (pintype "passive"))
      (node (ref "U2") (pin "85") (pinfunction "PD14_85") (pintype "passive"))
      (node (ref "U3") (pin "7") (pinfunction "I/O0_7") (pintype "passive"))
    )
    (net (code "22") (name "/FSMC_D1") (class "Default")
      (node (ref "LCM1") (pin "7") (pinfunction "DB1_7") (pintype "passive"))
      (node (ref "U2") (pin "86") (pinfunction "PD15_86") (pintype "passive"))
      (node (ref "U3") (pin "8") (pinfunction "I/O1_8") (pintype "passive"))
    )
    (net (code "23") (name "/FSMC_D2") (class "Default")
      (node (ref "LCM1") (pin "8") (pinfunction "DB2_8") (pintype "passive"))
      (node (ref "U2") (pin "114") (pinfunction "PD00_114") (pintype "passive"))
      (node (ref "U3") (pin "9") (pinfunction "I/O2_9") (pintype "passive"))
    )
    (net (code "24") (name "/FSMC_D3") (class "Default")
      (node (ref "LCM1") (pin "9") (pinfunction "DB3_9") (pintype "passive"))
      (node (ref "U2") (pin "115") (pinfunction "PD01_115") (pintype "passive"))
      (node (ref "U3") (pin "10") (pinfunction "I/O3_10") (pintype "passive"))
    )
    (net (code "25") (name "/FSMC_D4") (class "Default")
      (node (ref "LCM1") (pin "10") (pinfunction "DB4_10") (pintype "passive"))
      (node (ref "U2") (pin "58") (pinfunction "PE07_58") (pintype "passive"))
      (node (ref "U3") (pin "13") (pinfunction "I/O4_13") (pintype "passive"))
    )
    (net (code "26") (name "/FSMC_D5") (class "Default")
      (node (ref "LCM1") (pin "11") (pinfunction "DB5_11") (pintype "passive"))
      (node (ref "U2") (pin "59") (pinfunction "PE08_59") (pintype "passive"))
      (node (ref "U3") (pin "14") (pinfunction "I/O5_14") (pintype "passive"))
    )
    (net (code "27") (name "/FSMC_D6") (class "Default")
      (node (ref "LCM1") (pin "12") (pinfunction "DB6_12") (pintype "passive"))
      (node (ref "U2") (pin "60") (pinfunction "PE09_60") (pintype "passive"))
      (node (ref "U3") (pin "15") (pinfunction "I/O6_15") (pintype "passive"))
    )
    (net (code "28") (name "/FSMC_D7") (class "Default")
      (node (ref "LCM1") (pin "13") (pinfunction "DB7_13") (pintype "passive"))
      (node (ref "U2") (pin "63") (pinfunction "PE10_63") (pintype "passive"))
      (node (ref "U3") (pin "16") (pinfunction "I/O7_16") (pintype "passive"))
    )
    (net (code "29") (name "/FSMC_D8") (class "Default")
      (node (ref "LCM1") (pin "14") (pinfunction "DB8_14") (pintype "passive"))
      (node (ref "U2") (pin "64") (pinfunction "PE11_64") (pintype "passive"))
      (node (ref "U3") (pin "29") (pinfunction "I/O8_29") (pintype "passive"))
    )
    (net (code "30") (name "/FSMC_D9") (class "Default")
      (node (ref "LCM1") (pin "15") (pinfunction "DB9_15") (pintype "passive"))
      (node (ref "U2") (pin "65") (pinfunction "PE12_65") (pintype "passive"))
      (node (ref "U3") (pin "30") (pinfunction "I/O9_30") (pintype "passive"))
    )
    (net (code "31") (name "/FSMC_D10") (class "Default")
      (node (ref "LCM1") (pin "16") (pinfunction "DB10_16") (pintype "passive"))
      (node (ref "U2") (pin "66") (pinfunction "PE13_66") (pintype "passive"))
      (node (ref "U3") (pin "31") (pinfunction "I/O10_31") (pintype "passive"))
    )
    (net (code "32") (name "/FSMC_D11") (class "Default")
      (node (ref "LCM1") (pin "17") (pinfunction "DB11_17") (pintype "passive"))
      (node (ref "U2") (pin "67") (pinfunction "PE14_67") (pintype "passive"))
      (node (ref "U3") (pin "32") (pinfunction "I/O11_32") (pintype "passive"))
    )
    (net (code "33") (name "/FSMC_D12") (class "Default")
      (node (ref "LCM1") (pin "18") (pinfunction "DB12_18") (pintype "passive"))
      (node (ref "U2") (pin "68") (pinfunction "PE15_68") (pintype "passive"))
      (node (ref "U3") (pin "35") (pinfunction "I/O12_35") (pintype "passive"))
    )
    (net (code "34") (name "/FSMC_D13") (class "Default")
      (node (ref "LCM1") (pin "19") (pinfunction "DB13_19") (pintype "passive"))
      (node (ref "U2") (pin "77") (pinfunction "PD08_77") (pintype "passive"))
      (node (ref "U3") (pin "36") (pinfunction "I/O13_36") (pintype "passive"))
    )
    (net (code "35") (name "/FSMC_D14") (class "Default")
      (node (ref "LCM1") (pin "20") (pinfunction "DB14_20") (pintype "passive"))
      (node (ref "U2") (pin "78") (pinfunction "PD09_78") (pintype "passive"))
      (node (ref "U3") (pin "37") (pinfunction "I/O14_37") (pintype "passive"))
    )
    (net (code "36") (name "/FSMC_D15") (class "Default")
      (node (ref "LCM1") (pin "21") (pinfunction "DB15_21") (pintype "passive"))
      (node (ref "U2") (pin "79") (pinfunction "PD10_79") (pintype "passive"))
      (node (ref "U3") (pin "38") (pinfunction "I/O15_38") (pintype "passive"))
    )
    (net (code "37") (name "/FSMC_NBL0") (class "Default")
      (node (ref "U2") (pin "141") (pinfunction "PE00_141") (pintype "passive"))
      (node (ref "U3") (pin "39") (pinfunction "~{BLE}_39") (pintype "passive"))
    )
    (net (code "38") (name "/FSMC_NBL1") (class "Default")
      (node (ref "U2") (pin "142") (pinfunction "PE01_142") (pintype "passive"))
      (node (ref "U3") (pin "40") (pinfunction "~{BHE}_40") (pintype "passive"))
    )
    (net (code "39") (name "/FSMC_NE1") (class "Default")
      (node (ref "R3") (pin "1") (pinfunction "1_1") (pintype "passive"))
      (node (ref "U2") (pin "123") (pinfunction "PD07_123") (pintype "passive"))
      (node (ref "U3") (pin "6") (pinfunction "~{CE}_6") (pintype "passive"))
    )
    (net (code "40") (name "/FSMC_NE4") (class "Default")
      (node (ref "LCM1") (pin "1") (pinfunction "~{CS}_1") (pintype "passive"))
      (node (ref "U2") (pin "127") (pinfunction "PG12_127") (pintype "passive"))
    )
    (net (code "41") (name "/FSMC_NOE") (class "Default")
      (node (ref "LCM1") (pin "4") (pinfunction "~{RD}_4") (pintype "passive"))
      (node (ref "U2") (pin "118") (pinfunction "PD04_118") (pintype "passive"))
      (node (ref "U3") (pin "41") (pinfunction "~{OE}_41") (pintype "passive"))
    )
    (net (code "42") (name "/FSMC_NWE") (class "Default")
      (node (ref "LCM1") (pin "3") (pinfunction "~{WR}_3") (pintype "passive"))
      (node (ref "U2") (pin "119") (pinfunction "PD05_119") (pintype "passive"))
      (node (ref "U3") (pin "17") (pinfunction "~{WE}_17") (pintype "passive"))
    )
    (net (code "43") (name "/PA2_USART2_TX") (class "Default")
      (node (ref "R32") (pin "2") (pinfunction "2_2") (pintype "passive"))
      (node (ref "R46") (pin "2") (pinfunction "2_2") (pintype "passive"))
      (node (ref "U2") (pin "36") (pinfunction "PA02_36") (pintype "passive"))
    )
    (net (code "44") (name "/PA3_USART2_RX") (class "Default")
      (node (ref "R28") (pin "2") (pinfunction "2_2") (pintype "passive"))
      (node (ref "R43") (pin "2") (pinfunction "2_2") (pintype "passive"))
      (node (ref "U2") (pin "37") (pinfunction "PA03_37") (pintype "passive"))
    )
    (net (code "45") (name "/PA4_USART2_CK") (class "Default")
      (node (ref "R37") (pin "2") (pinfunction "2_2") (pintype "passive"))
      (node (ref "R49") (pin "2") (pinfunction "2_2") (pintype "passive"))
      (node (ref "U2") (pin "40") (pinfunction "PA04_40") (pintype "passive"))
    )
    (net (code "46") (name "/PA5_SPI1_SCK") (class "Default")
      (node (ref "R26") (pin "2") (pinfunction "2_2") (pintype "passive"))
      (node (ref "U2") (pin "41") (pinfunction "PA05_41") (pintype "passive"))
    )
    (net (code "47") (name "/PA6_SPI1_MISO") (class "Default")
      (node (ref "R30") (pin "2") (pinfunction "2_2") (pintype "passive"))
      (node (ref "U2") (pin "42") (pinfunction "PA06_42") (pintype "passive"))
    )
    (net (code "48") (name "/PA7_SPI1_MOSI") (class "Default")
      (node (ref "R35") (pin "2") (pinfunction "2_2") (pintype "passive"))
      (node (ref "U2") (pin "43") (pinfunction "PA07_43") (pintype "passive"))
    )
    (net (code "49") (name "/PA8_USART1_CX") (class "Default")
      (node (ref "R36") (pin "2") (pinfunction "2_2") (pintype "passive"))
      (node (ref "R41") (pin "2") (pinfunction "2_2") (pintype "passive"))
      (node (ref "U2") (pin "100") (pinfunction "PA08_100") (pintype "passive"))
    )
    (net (code "50") (name "/PA9_USART1_TX") (class "Default")
      (node (ref "R31") (pin "2") (pinfunction "2_2") (pintype "passive"))
      (node (ref "R40") (pin "2") (pinfunction "2_2") (pintype "passive"))
      (node (ref "U2") (pin "101") (pinfunction "PA09_101") (pintype "passive"))
    )
    (net (code "51") (name "/PA10_USART1_RX") (class "Default")
      (node (ref "R27") (pin "2") (pinfunction "2_2") (pintype "passive"))
      (node (ref "R39") (pin "2") (pinfunction "2_2") (pintype "passive"))
      (node (ref "U2") (pin "102") (pinfunction "PA10_102") (pintype "passive"))
    )
    (net (code "52") (name "/PA11_CAN1_RX") (class "Default")
      (node (ref "U2") (pin "103") (pinfunction "PA11_103") (pintype "passive"))
    )
    (net (code "53") (name "/PA12_CAN1_TX") (class "Default")
      (node (ref "U2") (pin "104") (pinfunction "PA12_104") (pintype "passive"))
    )
    (net (code "54") (name "/PA15_SPI1_NSS") (class "Default")
      (node (ref "R38") (pin "2") (pinfunction "2_2") (pintype "passive"))
      (node (ref "U2") (pin "110") (pinfunction "PA15_110") (pintype "passive"))
    )
    (net (code "55") (name "/PB4_KEY0") (class "Default")
      (node (ref "C42") (pin "1") (pinfunction "1_1") (pintype "passive"))
      (node (ref "R24") (pin "2") (pinfunction "2_2") (pintype "passive"))
      (node (ref "SW7") (pin "3") (pinfunction "3_3") (pintype "passive"))
      (node (ref "SW7") (pin "4") (pinfunction "4_4") (pintype "passive"))
      (node (ref "U2") (pin "134") (pinfunction "PB04_134") (pintype "passive"))
    )
    (net (code "56") (name "/PB5_KEY1") (class "Default")
      (node (ref "C43") (pin "1") (pinfunction "1_1") (pintype "passive"))
      (node (ref "R25") (pin "2") (pinfunction "2_2") (pintype "passive"))
      (node (ref "SW1") (pin "3") (pinfunction "3_3") (pintype "passive"))
      (node (ref "SW1") (pin "4") (pinfunction "4_4") (pintype "passive"))
      (node (ref "U2") (pin "135") (pinfunction "PB05_135") (pintype "passive"))
    )
    (net (code "57") (name "/PB6_TIM4_CH1") (class "Default")
      (node (ref "C25") (pin "1") (pinfunction "1_1") (pintype "passive"))
      (node (ref "R60") (pin "1") (pinfunction "1_1") (pintype "passive"))
      (node (ref "SW6") (pin "B") (pinfunction "B_B") (pintype "passive"))
      (node (ref "U2") (pin "136") (pinfunction "PB06_136") (pintype "passive"))
    )
    (net (code "58") (name "/PB7_TIM4_CH2") (class "Default")
      (node (ref "C24") (pin "1") (pinfunction "1_1") (pintype "passive"))
      (node (ref "R59") (pin "1") (pinfunction "1_1") (pintype "passive"))
      (node (ref "SW6") (pin "A") (pinfunction "A_A") (pintype "passive"))
      (node (ref "U2") (pin "137") (pinfunction "PB07_137") (pintype "passive"))
    )
    (net (code "59") (name "/PB8_I2C1_SCL") (class "Default")
      (node (ref "R51") (pin "2") (pinfunction "2_2") (pintype "passive"))
      (node (ref "R54") (pin "2") (pinfunction "2_2") (pintype "passive"))
      (node (ref "U2") (pin "139") (pinfunction "PB08_139") (pintype "passive"))
    )
    (net (code "60") (name "/PB9_I2C1_SDA") (class "Default")
      (node (ref "R53") (pin "2") (pinfunction "2_2") (pintype "passive"))
      (node (ref "R55") (pin "2") (pinfunction "2_2") (pintype "passive"))
      (node (ref "U2") (pin "140") (pinfunction "PB09_140") (pintype "passive"))
    )
    (net (code "61") (name "/PB10_USART3_TX") (class "Default")
      (node (ref "U2") (pin "69") (pinfunction "PB10_69") (pintype "passive"))
    )
    (net (code "62") (name "/PB11_USART3_RX") (class "Default")
      (node (ref "U2") (pin "70") (pinfunction "PB11_70") (pintype "passive"))
    )
    (net (code "63") (name "/PB12_SPI2_NSS") (class "Default")
      (node (ref "U2") (pin "73") (pinfunction "PB12_73") (pintype "passive"))
    )
    (net (code "64") (name "/PB13_SPI2_SCK") (class "Default")
      (node (ref "U2") (pin "74") (pinfunction "PB13_74") (pintype "passive"))
    )
    (net (code "65") (name "/PB15_LCD_BLK") (class "Default")
      (node (ref "LCM1") (pin "23") (pinfunction "BL_23") (pintype "passive"))
      (node (ref "U2") (pin "76") (pinfunction "PB15_76") (pintype "passive"))
    )
    (net (code "66") (name "/PC2_SPI2_MISO") (class "Default")
      (node (ref "U2") (pin "28") (pinfunction "PC02_28") (pintype "passive"))
    )
    (net (code "67") (name "/PC3_SPI2_MOSI") (class "Default")
      (node (ref "U2") (pin "29") (pinfunction "PC03_29") (pintype "passive"))
    )
    (net (code "68") (name "/PC6_USART6_TX") (class "Default")
      (node (ref "U2") (pin "96") (pinfunction "PC06_96") (pintype "passive"))
    )
    (net (code "69") (name "/PC7_USART6_RX") (class "Default")
      (node (ref "U2") (pin "97") (pinfunction "PC07_97") (pintype "passive"))
    )
    (net (code "70") (name "/PC8_485_CTR") (class "Default")
      (node (ref "U2") (pin "98") (pinfunction "PC08_98") (pintype "passive"))
    )
    (net (code "71") (name "/PE2_KEY2") (class "Default")
      (node (ref "C41") (pin "1") (pinfunction "1_1") (pintype "passive"))
      (node (ref "R23") (pin "2") (pinfunction "2_2") (pintype "passive"))
      (node (ref "SW2") (pin "3") (pinfunction "3_3") (pintype "passive"))
      (node (ref "SW2") (pin "4") (pinfunction "4_4") (pintype "passive"))
      (node (ref "U2") (pin "1") (pinfunction "PE02_1") (pintype "passive"))
    )
    (net (code "72") (name "/PE3_KEY3") (class "Default")
      (node (ref "C48") (pin "1") (pinfunction "1_1") (pintype "passive"))
      (node (ref "R33") (pin "2") (pinfunction "2_2") (pintype "passive"))
      (node (ref "SW3") (pin "3") (pinfunction "3_3") (pintype "passive"))
      (node (ref "SW3") (pin "4") (pinfunction "4_4") (pintype "passive"))
      (node (ref "U2") (pin "2") (pinfunction "PE03_2") (pintype "passive"))
    )
    (net (code "73") (name "/PE4_KEY4") (class "Default")
      (node (ref "C49") (pin "1") (pinfunction "1_1") (pintype "passive"))
      (node (ref "R34") (pin "2") (pinfunction "2_2") (pintype "passive"))
      (node (ref "SW4") (pin "3") (pinfunction "3_3") (pintype "passive"))
      (node (ref "SW4") (pin "4") (pinfunction "4_4") (pintype "passive"))
      (node (ref "U2") (pin "3") (pinfunction "PE04_3") (pintype "passive"))
    )
    (net (code "74") (name "/PE5_KEY5") (class "Default")
      (node (ref "C47") (pin "1") (pinfunction "1_1") (pintype "passive"))
      (node (ref "R29") (pin "2") (pinfunction "2_2") (pintype "passive"))
      (node (ref "SW5") (pin "3") (pinfunction "3_3") (pintype "passive"))
      (node (ref "SW5") (pin "4") (pinfunction "4_4") (pintype "passive"))
      (node (ref "U2") (pin "4") (pinfunction "PE05_4") (pintype "passive"))
    )
    (net (code "75") (name "/PE6_KEY6") (class "Default")
      (node (ref "C52") (pin "1") (pinfunction "1_1") (pintype "passive"))
      (node (ref "R44") (pin "1") (pinfunction "1_1") (pintype "passive"))
      (node (ref "SW6") (pin "D") (pinfunction "D_D") (pintype "passive"))
      (node (ref "U2") (pin "5") (pinfunction "PE06_5") (pintype "passive"))
    )
    (net (code "76") (name "/PF6_LED0") (class "Default")
      (node (ref "LED2") (pin "1") (pinfunction "K_1") (pintype "passive"))
      (node (ref "U2") (pin "18") (pinfunction "PF06_18") (pintype "passive"))
    )
    (net (code "77") (name "/PF7_LED1") (class "Default")
      (node (ref "LED3") (pin "1") (pinfunction "K_1") (pintype "passive"))
      (node (ref "U2") (pin "19") (pinfunction "PF07_19") (pintype "passive"))
    )
    (net (code "78") (name "/PF8_LED2") (class "Default")
      (node (ref "LED4") (pin "1") (pinfunction "K_1") (pintype "passive"))
      (node (ref "U2") (pin "20") (pinfunction "PF08_20") (pintype "passive"))
    )
    (net (code "79") (name "/PF9_LED3") (class "Default")
      (node (ref "LED5") (pin "1") (pinfunction "K_1") (pintype "passive"))
      (node (ref "U2") (pin "21") (pinfunction "PF09_21") (pintype "passive"))
    )
    (net (code "80") (name "/PF11_T_PENIRQ") (class "Default")
      (node (ref "U2") (pin "49") (pinfunction "PF11_49") (pintype "passive"))
    )
    (net (code "81") (name "/RESET") (class "Default")
      (node (ref "C12") (pin "2") (pinfunction "2_2") (pintype "passive"))
      (node (ref "LCM1") (pin "5") (pinfunction "~{RESET}_5") (pintype "passive"))
      (node (ref "R10") (pin "2") (pinfunction "2_2") (pintype "passive"))
      (node (ref "U2") (pin "25") (pinfunction "nRESET_25") (pintype "passive"))
    )
    (net (code "82") (name "/SWCLK") (class "Default")
      (node (ref "R20") (pin "1") (pinfunction "1_1") (pintype "passive"))
      (node (ref "U2") (pin "109") (pinfunction "PA14_109") (pintype "passive"))
    )
    (net (code "83") (name "/SWDIO") (class "Default")
      (node (ref "R19") (pin "1") (pinfunction "1_1") (pintype "passive"))
      (node (ref "U2") (pin "105") (pinfunction "PA13_105") (pintype "passive"))
    )
    (net (code "84") (name "/SWO") (class "Default")
      (node (ref "R21") (pin "1") (pinfunction "1_1") (pintype "passive"))
      (node (ref "U2") (pin "133") (pinfunction "PB03_133") (pintype "passive"))
    )
    (net (code "85") (name "3V3") (class "Default")
      (node (ref "C1") (pin "2") (pinfunction "2_2") (pintype "passive"))
      (node (ref "C13") (pin "2") (pinfunction "2_2") (pintype "passive"))
      (node (ref "C14") (pin "2") (pinfunction "2_2") (pintype "passive"))
      (node (ref "C18") (pin "2") (pinfunction "2_2") (pintype "passive"))
      (node (ref "C19") (pin "2") (pinfunction "2_2") (pintype "passive"))
      (node (ref "C2") (pin "2") (pinfunction "2_2") (pintype "passive"))
      (node (ref "C20") (pin "2") (pinfunction "2_2") (pintype "passive"))
      (node (ref "C21") (pin "2") (pinfunction "2_2") (pintype "passive"))
      (node (ref "C22") (pin "2") (pinfunction "2_2") (pintype "passive"))
      (node (ref "CN3") (pin "5") (pinfunction "5_5") (pintype "passive"))
      (node (ref "D1") (pin "2") (pinfunction "A_2") (pintype "passive"))
      (node (ref "L1") (pin "1") (pinfunction "1_1") (pintype "passive"))
      (node (ref "LCM1") (pin "24") (pinfunction "VDD_24") (pintype "passive"))
      (node (ref "R10") (pin "1") (pinfunction "1_1") (pintype "passive"))
      (node (ref "R23") (pin "1") (pinfunction "1_1") (pintype "passive"))
      (node (ref "R24") (pin "1") (pinfunction "1_1") (pintype "passive"))
      (node (ref "R25") (pin "1") (pinfunction "1_1") (pintype "passive"))
      (node (ref "R29") (pin "1") (pinfunction "1_1") (pintype "passive"))
      (node (ref "R3") (pin "2") (pinfunction "2_2") (pintype "passive"))
      (node (ref "R33") (pin "1") (pinfunction "1_1") (pintype "passive"))
      (node (ref "R34") (pin "1") (pinfunction "1_1") (pintype "passive"))
      (node (ref "R39") (pin "1") (pinfunction "1_1") (pintype "passive"))
      (node (ref "R40") (pin "1") (pinfunction "1_1") (pintype "passive"))
      (node (ref "R41") (pin "1") (pinfunction "1_1") (pintype "passive"))
      (node (ref "R42") (pin "1") (pinfunction "1_1") (pintype "passive"))
      (node (ref "R43") (pin "1") (pinfunction "1_1") (pintype "passive"))
      (node (ref "R44") (pin "2") (pinfunction "2_2") (pintype "passive"))
      (node (ref "R45") (pin "1") (pinfunction "1_1") (pintype "passive"))
      (node (ref "R46") (pin "1") (pinfunction "1_1") (pintype "passive"))
      (node (ref "R47") (pin "1") (pinfunction "1_1") (pintype "passive"))
      (node (ref "R48") (pin "1") (pinfunction "1_1") (pintype "passive"))
      (node (ref "R49") (pin "1") (pinfunction "1_1") (pintype "passive"))
      (node (ref "R54") (pin "1") (pinfunction "1_1") (pintype "passive"))
      (node (ref "R55") (pin "1") (pinfunction "1_1") (pintype "passive"))
      (node (ref "R59") (pin "2") (pinfunction "2_2") (pintype "passive"))
      (node (ref "R60") (pin "2") (pinfunction "2_2") (pintype "passive"))
      (node (ref "R8") (pin "2") (pinfunction "2_2") (pintype "passive"))
      (node (ref "U12") (pin "1") (pinfunction "1_1") (pintype "passive"))
      (node (ref "U13") (pin "1") (pinfunction "1_1") (pintype "passive"))
      (node (ref "U14") (pin "1") (pinfunction "1_1") (pintype "passive"))
      (node (ref "U19") (pin "1") (pinfunction "1_1") (pintype "passive"))
      (node (ref "U2") (pin "108") (pinfunction "VDD_108") (pintype "passive"))
      (node (ref "U2") (pin "121") (pinfunction "VDD_121") (pintype "passive"))
      (node (ref "U2") (pin "131") (pinfunction "VDD_131") (pintype "passive"))
      (node (ref "U2") (pin "143") (pinfunction "PDR_ON_143") (pintype "passive"))
      (node (ref "U2") (pin "144") (pinfunction "VDD_144") (pintype "passive"))
      (node (ref "U2") (pin "17") (pinfunction "VDD_17") (pintype "passive"))
      (node (ref "U2") (pin "30") (pinfunction "VDD_30") (pintype "passive"))
      (node (ref "U2") (pin "39") (pinfunction "VDD_39") (pintype "passive"))
      (node (ref "U2") (pin "52") (pinfunction "VDD_52") (pintype "passive"))
      (node (ref "U2") (pin "62") (pinfunction "VDD_62") (pintype "passive"))
      (node (ref "U2") (pin "72") (pinfunction "VDD_72") (pintype "passive"))
      (node (ref "U2") (pin "84") (pinfunction "VDD_84") (pintype "passive"))
      (node (ref "U2") (pin "95") (pinfunction "VDD_95") (pintype "passive"))
      (node (ref "U3") (pin "11") (pinfunction "VDD_11") (pintype "passive"))
      (node (ref "U3") (pin "33") (pinfunction "VDD_33") (pintype "passive"))
    )
    (net (code "86") (name "5V") (class "Default")
      (node (ref "U15") (pin "1") (pinfunction "1_1") (pintype "passive"))
      (node (ref "U16") (pin "1") (pinfunction "1_1") (pintype "passive"))
      (node (ref "U17") (pin "1") (pinfunction "1_1") (pintype "passive"))
      (node (ref "U21") (pin "1") (pinfunction "1_1") (pintype "passive"))
    )
    (net (code "87") (name "A3V3") (class "Default")
      (node (ref "C15") (pin "2") (pinfunction "2_2") (pintype "passive"))
      (node (ref "L1") (pin "2") (pinfunction "2_2") (pintype "passive"))
      (node (ref "L2") (pin "1") (pinfunction "1_1") (pintype "passive"))
      (node (ref "U2") (pin "33") (pinfunction "VDDA_33") (pintype "passive"))
    )
    (net (code "88") (name "AGND") (class "Default")
      (node (ref "BT1") (pin "2") (pinfunction "2_2") (pintype "passive"))
      (node (ref "C1") (pin "1") (pinfunction "1_1") (pintype "passive"))
      (node (ref "C10") (pin "1") (pinfunction "1_1") (pintype "passive"))
      (node (ref "C11") (pin "1") (pinfunction "1_1") (pintype "passive"))
      (node (ref "C12") (pin "1") (pinfunction "1_1") (pintype "passive"))
      (node (ref "C13") (pin "1") (pinfunction "1_1") (pintype "passive"))
      (node (ref "C14") (pin "1") (pinfunction "1_1") (pintype "passive"))
      (node (ref "C15") (pin "1") (pinfunction "1_1") (pintype "passive"))
      (node (ref "C16") (pin "1") (pinfunction "1_1") (pintype "passive"))
      (node (ref "C18") (pin "1") (pinfunction "1_1") (pintype "passive"))
      (node (ref "C19") (pin "1") (pinfunction "1_1") (pintype "passive"))
      (node (ref "C2") (pin "1") (pinfunction "1_1") (pintype "passive"))
      (node (ref "C20") (pin "1") (pinfunction "1_1") (pintype "passive"))
      (node (ref "C21") (pin "1") (pinfunction "1_1") (pintype "passive"))
      (node (ref "C22") (pin "1") (pinfunction "1_1") (pintype "passive"))
      (node (ref "C24") (pin "2") (pinfunction "2_2") (pintype "passive"))
      (node (ref "C25") (pin "2") (pinfunction "2_2") (pintype "passive"))
      (node (ref "C41") (pin "2") (pinfunction "2_2") (pintype "passive"))
      (node (ref "C42") (pin "2") (pinfunction "2_2") (pintype "passive"))
      (node (ref "C43") (pin "2") (pinfunction "2_2") (pintype "passive"))
      (node (ref "C44") (pin "1") (pinfunction "1_1") (pintype "passive"))
      (node (ref "C45") (pin "1") (pinfunction "1_1") (pintype "passive"))
      (node (ref "C46") (pin "1") (pinfunction "1_1") (pintype "passive"))
      (node (ref "C47") (pin "2") (pinfunction "2_2") (pintype "passive"))
      (node (ref "C48") (pin "2") (pinfunction "2_2") (pintype "passive"))
      (node (ref "C49") (pin "2") (pinfunction "2_2") (pintype "passive"))
      (node (ref "C50") (pin "1") (pinfunction "1_1") (pintype "passive"))
      (node (ref "C52") (pin "2") (pinfunction "2_2") (pintype "passive"))
      (node (ref "C6") (pin "2") (pinfunction "2_2") (pintype "passive"))
      (node (ref "C7") (pin "2") (pinfunction "2_2") (pintype "passive"))
      (node (ref "C8") (pin "1") (pinfunction "1_1") (pintype "passive"))
      (node (ref "C9") (pin "1") (pinfunction "1_1") (pintype "passive"))
      (node (ref "CN3") (pin "4") (pinfunction "4_4") (pintype "passive"))
      (node (ref "CN4") (pin "2") (pinfunction "2_2") (pintype "passive"))
      (node (ref "CN5") (pin "2") (pinfunction "2_2") (pintype "passive"))
      (node (ref "CN6") (pin "2") (pinfunction "2_2") (pintype "passive"))
      (node (ref "CN8") (pin "2") (pinfunction "2_2") (pintype "passive"))
      (node (ref "D10") (pin "1") (pinfunction "A_1") (pintype "passive"))
      (node (ref "D11") (pin "1") (pinfunction "A_1") (pintype "passive"))
      (node (ref "D12") (pin "1") (pinfunction "A_1") (pintype "passive"))
      (node (ref "D13") (pin "1") (pinfunction "A_1") (pintype "passive"))
      (node (ref "D14") (pin "1") (pinfunction "A_1") (pintype "passive"))
      (node (ref "D15") (pin "1") (pinfunction "A_1") (pintype "passive"))
      (node (ref "D16") (pin "1") (pinfunction "A_1") (pintype "passive"))
      (node (ref "D17") (pin "1") (pinfunction "A_1") (pintype "passive"))
      (node (ref "D18") (pin "1") (pinfunction "A_1") (pintype "passive"))
      (node (ref "D19") (pin "1") (pinfunction "A_1") (pintype "passive"))
      (node (ref "D21") (pin "2") (pinfunction "K_2") (pintype "passive"))
      (node (ref "D24") (pin "1") (pinfunction "A_1") (pintype "passive"))
      (node (ref "D25") (pin "1") (pinfunction "A_1") (pintype "passive"))
      (node (ref "D26") (pin "1") (pinfunction "A_1") (pintype "passive"))
      (node (ref "D27") (pin "1") (pinfunction "A_1") (pintype "passive"))
      (node (ref "D28") (pin "1") (pinfunction "A_1") (pintype "passive"))
      (node (ref "D6") (pin "2") (pinfunction "K_2") (pintype "passive"))
      (node (ref "D8") (pin "2") (pinfunction "K_2") (pintype "passive"))
      (node (ref "D9") (pin "2") (pinfunction "K_2") (pintype "passive"))
      (node (ref "LCM1") (pin "22") (pinfunction "GND_22") (pintype "passive"))
      (node (ref "R9") (pin "2") (pinfunction "2_2") (pintype "passive"))
      (node (ref "SW1") (pin "1") (pinfunction "1_1") (pintype "passive"))
      (node (ref "SW1") (pin "2") (pinfunction "2_2") (pintype "passive"))
      (node (ref "SW2") (pin "1") (pinfunction "1_1") (pintype "passive"))
      (node (ref "SW2") (pin "2") (pinfunction "2_2") (pintype "passive"))
      (node (ref "SW3") (pin "1") (pinfunction "1_1") (pintype "passive"))
      (node (ref "SW3") (pin "2") (pinfunction "2_2") (pintype "passive"))
      (node (ref "SW4") (pin "1") (pinfunction "1_1") (pintype "passive"))
      (node (ref "SW4") (pin "2") (pinfunction "2_2") (pintype "passive"))
      (node (ref "SW5") (pin "1") (pinfunction "1_1") (pintype "passive"))
      (node (ref "SW5") (pin "2") (pinfunction "2_2") (pintype "passive"))
      (node (ref "SW6") (pin "C") (pinfunction "C_C") (pintype "passive"))
      (node (ref "SW6") (pin "E") (pinfunction "E_E") (pintype "passive"))
      (node (ref "SW6") (pin "MH1") (pinfunction "MH1_MH1") (pintype "passive"))
      (node (ref "SW6") (pin "MH2") (pinfunction "MH2_MH2") (pintype "passive"))
      (node (ref "SW7") (pin "1") (pinfunction "1_1") (pintype "passive"))
      (node (ref "SW7") (pin "2") (pinfunction "2_2") (pintype "passive"))
      (node (ref "U2") (pin "107") (pinfunction "VSS_107") (pintype "passive"))
      (node (ref "U2") (pin "120") (pinfunction "VSS_120") (pintype "passive"))
      (node (ref "U2") (pin "130") (pinfunction "VSS_130") (pintype "passive"))
      (node (ref "U2") (pin "16") (pinfunction "VSS_16") (pintype "passive"))
      (node (ref "U2") (pin "31") (pinfunction "VSSA_31") (pintype "passive"))
      (node (ref "U2") (pin "38") (pinfunction "VSS_38") (pintype "passive"))
      (node (ref "U2") (pin "51") (pinfunction "VSS_51") (pintype "passive"))
      (node (ref "U2") (pin "61") (pinfunction "VSS_61") (pintype "passive"))
      (node (ref "U2") (pin "83") (pinfunction "VSS_83") (pintype "passive"))
      (node (ref "U2") (pin "94") (pinfunction "VSS_94") (pintype "passive"))
      (node (ref "U3") (pin "12") (pinfunction "VSS_12") (pintype "passive"))
      (node (ref "U3") (pin "34") (pinfunction "VSS_34") (pintype "passive"))
      (node (ref "X1") (pin "2") (pinfunction "GND_2") (pintype "passive"))
      (node (ref "X1") (pin "4") (pinfunction "GND_4") (pintype "passive"))
    )
    (net (code "89") (name "Net-(D1-K)") (class "Default")
      (node (ref "D1") (pin "1") (pinfunction "K_1") (pintype "passive"))
      (node (ref "D2") (pin "1") (pinfunction "K_1") (pintype "passive"))
      (node (ref "U2") (pin "6") (pinfunction "Vbat_6") (pintype "passive"))
    )
    (net (code "90") (name "Net-(D2-A)") (class "Default")
      (node (ref "BT1") (pin "1") (pinfunction "1_1") (pintype "passive"))
      (node (ref "D2") (pin "2") (pinfunction "A_2") (pintype "passive"))
    )
    (net (code "91") (name "Net-(D6-A)") (class "Default")
      (node (ref "C46") (pin "2") (pinfunction "2_2") (pintype "passive"))
      (node (ref "CN5") (pin "1") (pinfunction "1_1") (pintype "passive"))
      (node (ref "D6") (pin "1") (pinfunction "A_1") (pintype "passive"))
      (node (ref "U12") (pin "2") (pinfunction "2_2") (pintype "passive"))
      (node (ref "U15") (pin "2") (pinfunction "2_2") (pintype "passive"))
    )
    (net (code "92") (name "Net-(D8-A)") (class "Default")
      (node (ref "C44") (pin "2") (pinfunction "2_2") (pintype "passive"))
      (node (ref "CN4") (pin "1") (pinfunction "1_1") (pintype "passive"))
      (node (ref "D8") (pin "1") (pinfunction "A_1") (pintype "passive"))
      (node (ref "U13") (pin "2") (pinfunction "2_2") (pintype "passive"))
      (node (ref "U16") (pin "2") (pinfunction "2_2") (pintype "passive"))
    )
    (net (code "93") (name "Net-(D9-A)") (class "Default")
      (node (ref "C45") (pin "2") (pinfunction "2_2") (pintype "passive"))
      (node (ref "CN6") (pin "1") (pinfunction "1_1") (pintype "passive"))
      (node (ref "D9") (pin "1") (pinfunction "A_1") (pintype "passive"))
      (node (ref "U14") (pin "2") (pinfunction "2_2") (pintype "passive"))
      (node (ref "U17") (pin "2") (pinfunction "2_2") (pintype "passive"))
    )
    (net (code "94") (name "Net-(D10-K)") (class "Default")
      (node (ref "CN4") (pin "3") (pinfunction "3_3") (pintype "passive"))
      (node (ref "D10") (pin "2") (pinfunction "K_2") (pintype "passive"))
      (node (ref "R27") (pin "1") (pinfunction "1_1") (pintype "passive"))
    )
    (net (code "95") (name "Net-(D11-K)") (class "Default")
      (node (ref "CN4") (pin "4") (pinfunction "4_4") (pintype "passive"))
      (node (ref "D11") (pin "2") (pinfunction "K_2") (pintype "passive"))
      (node (ref "R31") (pin "1") (pinfunction "1_1") (pintype "passive"))
    )
    (net (code "96") (name "Net-(D12-K)") (class "Default")
      (node (ref "CN4") (pin "5") (pinfunction "5_5") (pintype "passive"))
      (node (ref "D12") (pin "2") (pinfunction "K_2") (pintype "passive"))
      (node (ref "R36") (pin "1") (pinfunction "1_1") (pintype "passive"))
    )
    (net (code "97") (name "Net-(D13-K)") (class "Default")
      (node (ref "CN6") (pin "3") (pinfunction "3_3") (pintype "passive"))
      (node (ref "D13") (pin "2") (pinfunction "K_2") (pintype "passive"))
      (node (ref "R28") (pin "1") (pinfunction "1_1") (pintype "passive"))
    )
    (net (code "98") (name "Net-(D14-K)") (class "Default")
      (node (ref "CN6") (pin "4") (pinfunction "4_4") (pintype "passive"))
      (node (ref "D14") (pin "2") (pinfunction "K_2") (pintype "passive"))
      (node (ref "R32") (pin "1") (pinfunction "1_1") (pintype "passive"))
    )
    (net (code "99") (name "Net-(D15-K)") (class "Default")
      (node (ref "CN6") (pin "5") (pinfunction "5_5") (pintype "passive"))
      (node (ref "D15") (pin "2") (pinfunction "K_2") (pintype "passive"))
      (node (ref "R37") (pin "1") (pinfunction "1_1") (pintype "passive"))
    )
    (net (code "100") (name "Net-(D16-K)") (class "Default")
      (node (ref "CN5") (pin "6") (pinfunction "6_6") (pintype "passive"))
      (node (ref "D16") (pin "2") (pinfunction "K_2") (pintype "passive"))
      (node (ref "R38") (pin "1") (pinfunction "1_1") (pintype "passive"))
    )
    (net (code "101") (name "Net-(D17-K)") (class "Default")
      (node (ref "CN5") (pin "5") (pinfunction "5_5") (pintype "passive"))
      (node (ref "D17") (pin "2") (pinfunction "K_2") (pintype "passive"))
      (node (ref "R35") (pin "1") (pinfunction "1_1") (pintype "passive"))
    )
    (net (code "102") (name "Net-(D18-K)") (class "Default")
      (node (ref "CN5") (pin "4") (pinfunction "4_4") (pintype "passive"))
      (node (ref "D18") (pin "2") (pinfunction "K_2") (pintype "passive"))
      (node (ref "R30") (pin "1") (pinfunction "1_1") (pintype "passive"))
    )
    (net (code "103") (name "Net-(D19-K)") (class "Default")
      (node (ref "CN5") (pin "3") (pinfunction "3_3") (pintype "passive"))
      (node (ref "D19") (pin "2") (pinfunction "K_2") (pintype "passive"))
      (node (ref "R26") (pin "1") (pinfunction "1_1") (pintype "passive"))
    )
    (net (code "104") (name "Net-(D21-A)") (class "Default")
      (node (ref "C50") (pin "2") (pinfunction "2_2") (pintype "passive"))
      (node (ref "CN8") (pin "1") (pinfunction "1_1") (pintype "passive"))
      (node (ref "D21") (pin "1") (pinfunction "A_1") (pintype "passive"))
      (node (ref "U19") (pin "2") (pinfunction "2_2") (pintype "passive"))
      (node (ref "U21") (pin "2") (pinfunction "2_2") (pintype "passive"))
    )
    (net (code "105") (name "Net-(D24-K)") (class "Default")
      (node (ref "CN8") (pin "3") (pinfunction "3_3") (pintype "passive"))
      (node (ref "D24") (pin "2") (pinfunction "K_2") (pintype "passive"))
      (node (ref "R51") (pin "1") (pinfunction "1_1") (pintype "passive"))
    )
    (net (code "106") (name "Net-(D25-K)") (class "Default")
      (node (ref "CN8") (pin "4") (pinfunction "4_4") (pintype "passive"))
      (node (ref "D25") (pin "2") (pinfunction "K_2") (pintype "passive"))
      (node (ref "R53") (pin "1") (pinfunction "1_1") (pintype "passive"))
    )
    (net (code "107") (name "Net-(D26-K)") (class "Default")
      (node (ref "CN3") (pin "3") (pinfunction "3_3") (pintype "passive"))
      (node (ref "D26") (pin "2") (pinfunction "K_2") (pintype "passive"))
      (node (ref "R19") (pin "2") (pinfunction "2_2") (pintype "passive"))
    )
    (net (code "108") (name "Net-(D27-K)") (class "Default")
      (node (ref "CN3") (pin "2") (pinfunction "2_2") (pintype "passive"))
      (node (ref "D27") (pin "2") (pinfunction "K_2") (pintype "passive"))
      (node (ref "R20") (pin "2") (pinfunction "2_2") (pintype "passive"))
    )
    (net (code "109") (name "Net-(D28-K)") (class "Default")
      (node (ref "CN3") (pin "1") (pinfunction "1_1") (pintype "passive"))
      (node (ref "D28") (pin "2") (pinfunction "K_2") (pintype "passive"))
      (node (ref "R21") (pin "2") (pinfunction "2_2") (pintype "passive"))
    )
    (net (code "110") (name "Net-(LED2-A)") (class "Default")
      (node (ref "LED2") (pin "2") (pinfunction "A_2") (pintype "passive"))
      (node (ref "R42") (pin "2") (pinfunction "2_2") (pintype "passive"))
    )
    (net (code "111") (name "Net-(LED3-A)") (class "Default")
      (node (ref "LED3") (pin "2") (pinfunction "A_2") (pintype "passive"))
      (node (ref "R45") (pin "2") (pinfunction "2_2") (pintype "passive"))
    )
    (net (code "112") (name "Net-(LED4-A)") (class "Default")
      (node (ref "LED4") (pin "2") (pinfunction "A_2") (pintype "passive"))
      (node (ref "R47") (pin "2") (pinfunction "2_2") (pintype "passive"))
    )
    (net (code "113") (name "Net-(LED5-A)") (class "Default")
      (node (ref "LED5") (pin "2") (pinfunction "A_2") (pintype "passive"))
      (node (ref "R48") (pin "2") (pinfunction "2_2") (pintype "passive"))
    )
    (net (code "114") (name "Net-(U2A-PC14)") (class "Default")
      (node (ref "C8") (pin "2") (pinfunction "2_2") (pintype "passive"))
      (node (ref "U2") (pin "8") (pinfunction "PC14_8") (pintype "passive"))
      (node (ref "X2") (pin "1") (pinfunction "1_1") (pintype "passive"))
    )
    (net (code "115") (name "Net-(U2A-PC15)") (class "Default")
      (node (ref "C9") (pin "2") (pinfunction "2_2") (pintype "passive"))
      (node (ref "U2") (pin "9") (pinfunction "PC15_9") (pintype "passive"))
      (node (ref "X2") (pin "2") (pinfunction "2_2") (pintype "passive"))
    )
    (net (code "116") (name "Net-(U2B-OSC_IN)") (class "Default")
      (node (ref "C6") (pin "1") (pinfunction "1_1") (pintype "passive"))
      (node (ref "U2") (pin "23") (pinfunction "OSC_IN_23") (pintype "passive"))
      (node (ref "X1") (pin "3") (pinfunction "3_3") (pintype "passive"))
    )
    (net (code "117") (name "Net-(U2B-OSC_OUT)") (class "Default")
      (node (ref "C7") (pin "1") (pinfunction "1_1") (pintype "passive"))
      (node (ref "U2") (pin "24") (pinfunction "OSC_OUT_24") (pintype "passive"))
      (node (ref "X1") (pin "1") (pinfunction "1_1") (pintype "passive"))
    )
    (net (code "118") (name "Net-(U2B-VCAP_1)") (class "Default")
      (node (ref "C11") (pin "2") (pinfunction "2_2") (pintype "passive"))
      (node (ref "U2") (pin "71") (pinfunction "VCAP_1_71") (pintype "passive"))
    )
    (net (code "119") (name "Net-(U2B-VCAP_2)") (class "Default")
      (node (ref "C10") (pin "2") (pinfunction "2_2") (pintype "passive"))
      (node (ref "U2") (pin "106") (pinfunction "VCAP_2_106") (pintype "passive"))
    )
    (net (code "120") (name "Vref") (class "Default")
      (node (ref "C16") (pin "2") (pinfunction "2_2") (pintype "passive"))
      (node (ref "L2") (pin "2") (pinfunction "2_2") (pintype "passive"))
      (node (ref "U2") (pin "32") (pinfunction "VREF+_32") (pintype "passive"))
    )
    (net (code "121") (name "unconnected-(LG1-Pad0)") (class "Default")
      (node (ref "LG1") (pin "0") (pinfunction "0_0") (pintype "passive"))
    )
    (net (code "122") (name "unconnected-(LG1-Pad0)_1") (class "Default")
      (node (ref "LG1") (pin "0") (pinfunction "0_0") (pintype "passive"))
    )
    (net (code "123") (name "unconnected-(LG1-Pad0)_2") (class "Default")
      (node (ref "LG1") (pin "0") (pinfunction "0_0") (pintype "passive"))
    )
    (net (code "124") (name "unconnected-(LG1-Pad0)_3") (class "Default")
      (node (ref "LG1") (pin "0") (pinfunction "0_0") (pintype "passive"))
    )
    (net (code "125") (name "unconnected-(LG2-Pad0)") (class "Default")
      (node (ref "LG2") (pin "0") (pinfunction "0_0") (pintype "passive"))
    )
    (net (code "126") (name "unconnected-(LG2-Pad0)_1") (class "Default")
      (node (ref "LG2") (pin "0") (pinfunction "0_0") (pintype "passive"))
    )
    (net (code "127") (name "unconnected-(LG2-Pad0)_2") (class "Default")
      (node (ref "LG2") (pin "0") (pinfunction "0_0") (pintype "passive"))
    )
    (net (code "128") (name "unconnected-(LG2-Pad0)_3") (class "Default")
      (node (ref "LG2") (pin "0") (pinfunction "0_0") (pintype "passive"))
    )
    (net (code "129") (name "unconnected-(LG3-Pad0)") (class "Default")
      (node (ref "LG3") (pin "0") (pinfunction "0_0") (pintype "passive"))
    )
    (net (code "130") (name "unconnected-(LG3-Pad0)_1") (class "Default")
      (node (ref "LG3") (pin "0") (pinfunction "0_0") (pintype "passive"))
    )
    (net (code "131") (name "unconnected-(LG3-Pad0)_2") (class "Default")
      (node (ref "LG3") (pin "0") (pinfunction "0_0") (pintype "passive"))
    )
    (net (code "132") (name "unconnected-(LG3-Pad0)_3") (class "Default")
      (node (ref "LG3") (pin "0") (pinfunction "0_0") (pintype "passive"))
    )
    (net (code "133") (name "unconnected-(LG4-Pad0)") (class "Default")
      (node (ref "LG4") (pin "0") (pinfunction "0_0") (pintype "passive"))
    )
    (net (code "134") (name "unconnected-(LG4-Pad0)_1") (class "Default")
      (node (ref "LG4") (pin "0") (pinfunction "0_0") (pintype "passive"))
    )
    (net (code "135") (name "unconnected-(LG4-Pad0)_2") (class "Default")
      (node (ref "LG4") (pin "0") (pinfunction "0_0") (pintype "passive"))
    )
    (net (code "136") (name "unconnected-(LG4-Pad0)_3") (class "Default")
      (node (ref "LG4") (pin "0") (pinfunction "0_0") (pintype "passive"))
    )
    (net (code "137") (name "unconnected-(U2A-PA00-Pad34)") (class "Default")
      (node (ref "U2") (pin "34") (pinfunction "PA00_34") (pintype "passive"))
    )
    (net (code "138") (name "unconnected-(U2A-PA01-Pad35)") (class "Default")
      (node (ref "U2") (pin "35") (pinfunction "PA01_35") (pintype "passive"))
    )
    (net (code "139") (name "unconnected-(U2A-PB00-Pad46)") (class "Default")
      (node (ref "U2") (pin "46") (pinfunction "PB00_46") (pintype "passive"))
    )
    (net (code "140") (name "unconnected-(U2A-PB01-Pad47)") (class "Default")
      (node (ref "U2") (pin "47") (pinfunction "PB01_47") (pintype "passive"))
    )
    (net (code "141") (name "unconnected-(U2A-PB02-Pad48)") (class "Default")
      (node (ref "U2") (pin "48") (pinfunction "PB02_48") (pintype "passive"))
    )
    (net (code "142") (name "unconnected-(U2A-PB14-Pad75)") (class "Default")
      (node (ref "U2") (pin "75") (pinfunction "PB14_75") (pintype "passive"))
    )
    (net (code "143") (name "unconnected-(U2A-PC00-Pad26)") (class "Default")
      (node (ref "U2") (pin "26") (pinfunction "PC00_26") (pintype "passive"))
    )
    (net (code "144") (name "unconnected-(U2A-PC01-Pad27)") (class "Default")
      (node (ref "U2") (pin "27") (pinfunction "PC01_27") (pintype "passive"))
    )
    (net (code "145") (name "unconnected-(U2A-PC04-Pad44)") (class "Default")
      (node (ref "U2") (pin "44") (pinfunction "PC04_44") (pintype "passive"))
    )
    (net (code "146") (name "unconnected-(U2A-PC05-Pad45)") (class "Default")
      (node (ref "U2") (pin "45") (pinfunction "PC05_45") (pintype "passive"))
    )
    (net (code "147") (name "unconnected-(U2A-PC09-Pad99)") (class "Default")
      (node (ref "U2") (pin "99") (pinfunction "PC09_99") (pintype "passive"))
    )
    (net (code "148") (name "unconnected-(U2A-PC10-Pad111)") (class "Default")
      (node (ref "U2") (pin "111") (pinfunction "PC10_111") (pintype "passive"))
    )
    (net (code "149") (name "unconnected-(U2A-PC11-Pad112)") (class "Default")
      (node (ref "U2") (pin "112") (pinfunction "PC11_112") (pintype "passive"))
    )
    (net (code "150") (name "unconnected-(U2A-PC12-Pad113)") (class "Default")
      (node (ref "U2") (pin "113") (pinfunction "PC12_113") (pintype "passive"))
    )
    (net (code "151") (name "unconnected-(U2A-PC13-Pad7)") (class "Default")
      (node (ref "U2") (pin "7") (pinfunction "PC13_7") (pintype "passive"))
    )
    (net (code "152") (name "unconnected-(U2A-PD02-Pad116)") (class "Default")
      (node (ref "U2") (pin "116") (pinfunction "PD02_116") (pintype "passive"))
    )
    (net (code "153") (name "unconnected-(U2A-PD03-Pad117)") (class "Default")
      (node (ref "U2") (pin "117") (pinfunction "PD03_117") (pintype "passive"))
    )
    (net (code "154") (name "unconnected-(U2A-PD06-Pad122)") (class "Default")
      (node (ref "U2") (pin "122") (pinfunction "PD06_122") (pintype "passive"))
    )
    (net (code "155") (name "unconnected-(U2A-PF10-Pad22)") (class "Default")
      (node (ref "U2") (pin "22") (pinfunction "PF10_22") (pintype "passive"))
    )
    (net (code "156") (name "unconnected-(U2A-PG06-Pad91)") (class "Default")
      (node (ref "U2") (pin "91") (pinfunction "PG06_91") (pintype "passive"))
    )
    (net (code "157") (name "unconnected-(U2A-PG07-Pad92)") (class "Default")
      (node (ref "U2") (pin "92") (pinfunction "PG07_92") (pintype "passive"))
    )
    (net (code "158") (name "unconnected-(U2A-PG08-Pad93)") (class "Default")
      (node (ref "U2") (pin "93") (pinfunction "PG08_93") (pintype "passive"))
    )
    (net (code "159") (name "unconnected-(U2A-PG09-Pad124)") (class "Default")
      (node (ref "U2") (pin "124") (pinfunction "PG09_124") (pintype "passive"))
    )
    (net (code "160") (name "unconnected-(U2A-PG10-Pad125)") (class "Default")
      (node (ref "U2") (pin "125") (pinfunction "PG10_125") (pintype "passive"))
    )
    (net (code "161") (name "unconnected-(U2A-PG11-Pad126)") (class "Default")
      (node (ref "U2") (pin "126") (pinfunction "PG11_126") (pintype "passive"))
    )
    (net (code "162") (name "unconnected-(U2A-PG13-Pad128)") (class "Default")
      (node (ref "U2") (pin "128") (pinfunction "PG13_128") (pintype "passive"))
    )
    (net (code "163") (name "unconnected-(U2A-PG14-Pad129)") (class "Default")
      (node (ref "U2") (pin "129") (pinfunction "PG14_129") (pintype "passive"))
    )
    (net (code "164") (name "unconnected-(U2A-PG15-Pad132)") (class "Default")
      (node (ref "U2") (pin "132") (pinfunction "PG15_132") (pintype "passive"))
    )
  )
)
